# Amplifier_Mixer.net
KiCad netlist of a schematic drawn in EAGLE
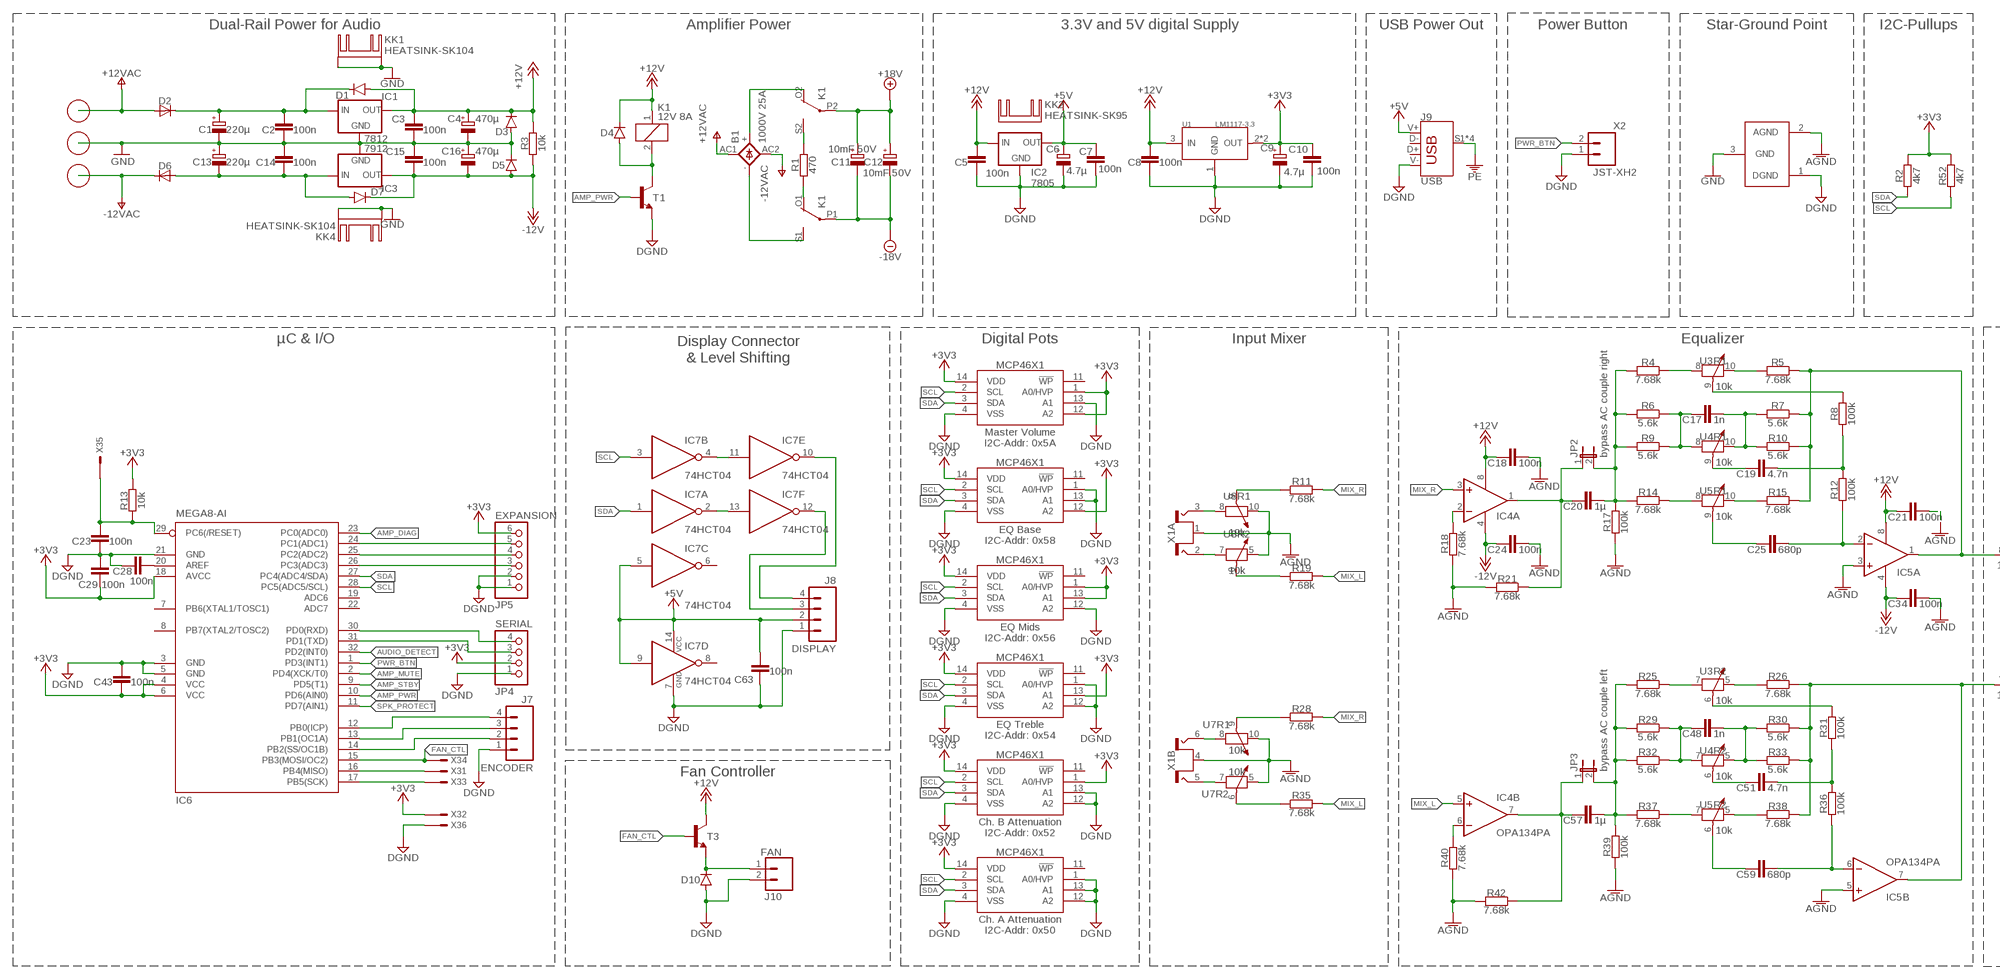
[diagram p0: schematic, sheet 1, part 1 of 2]
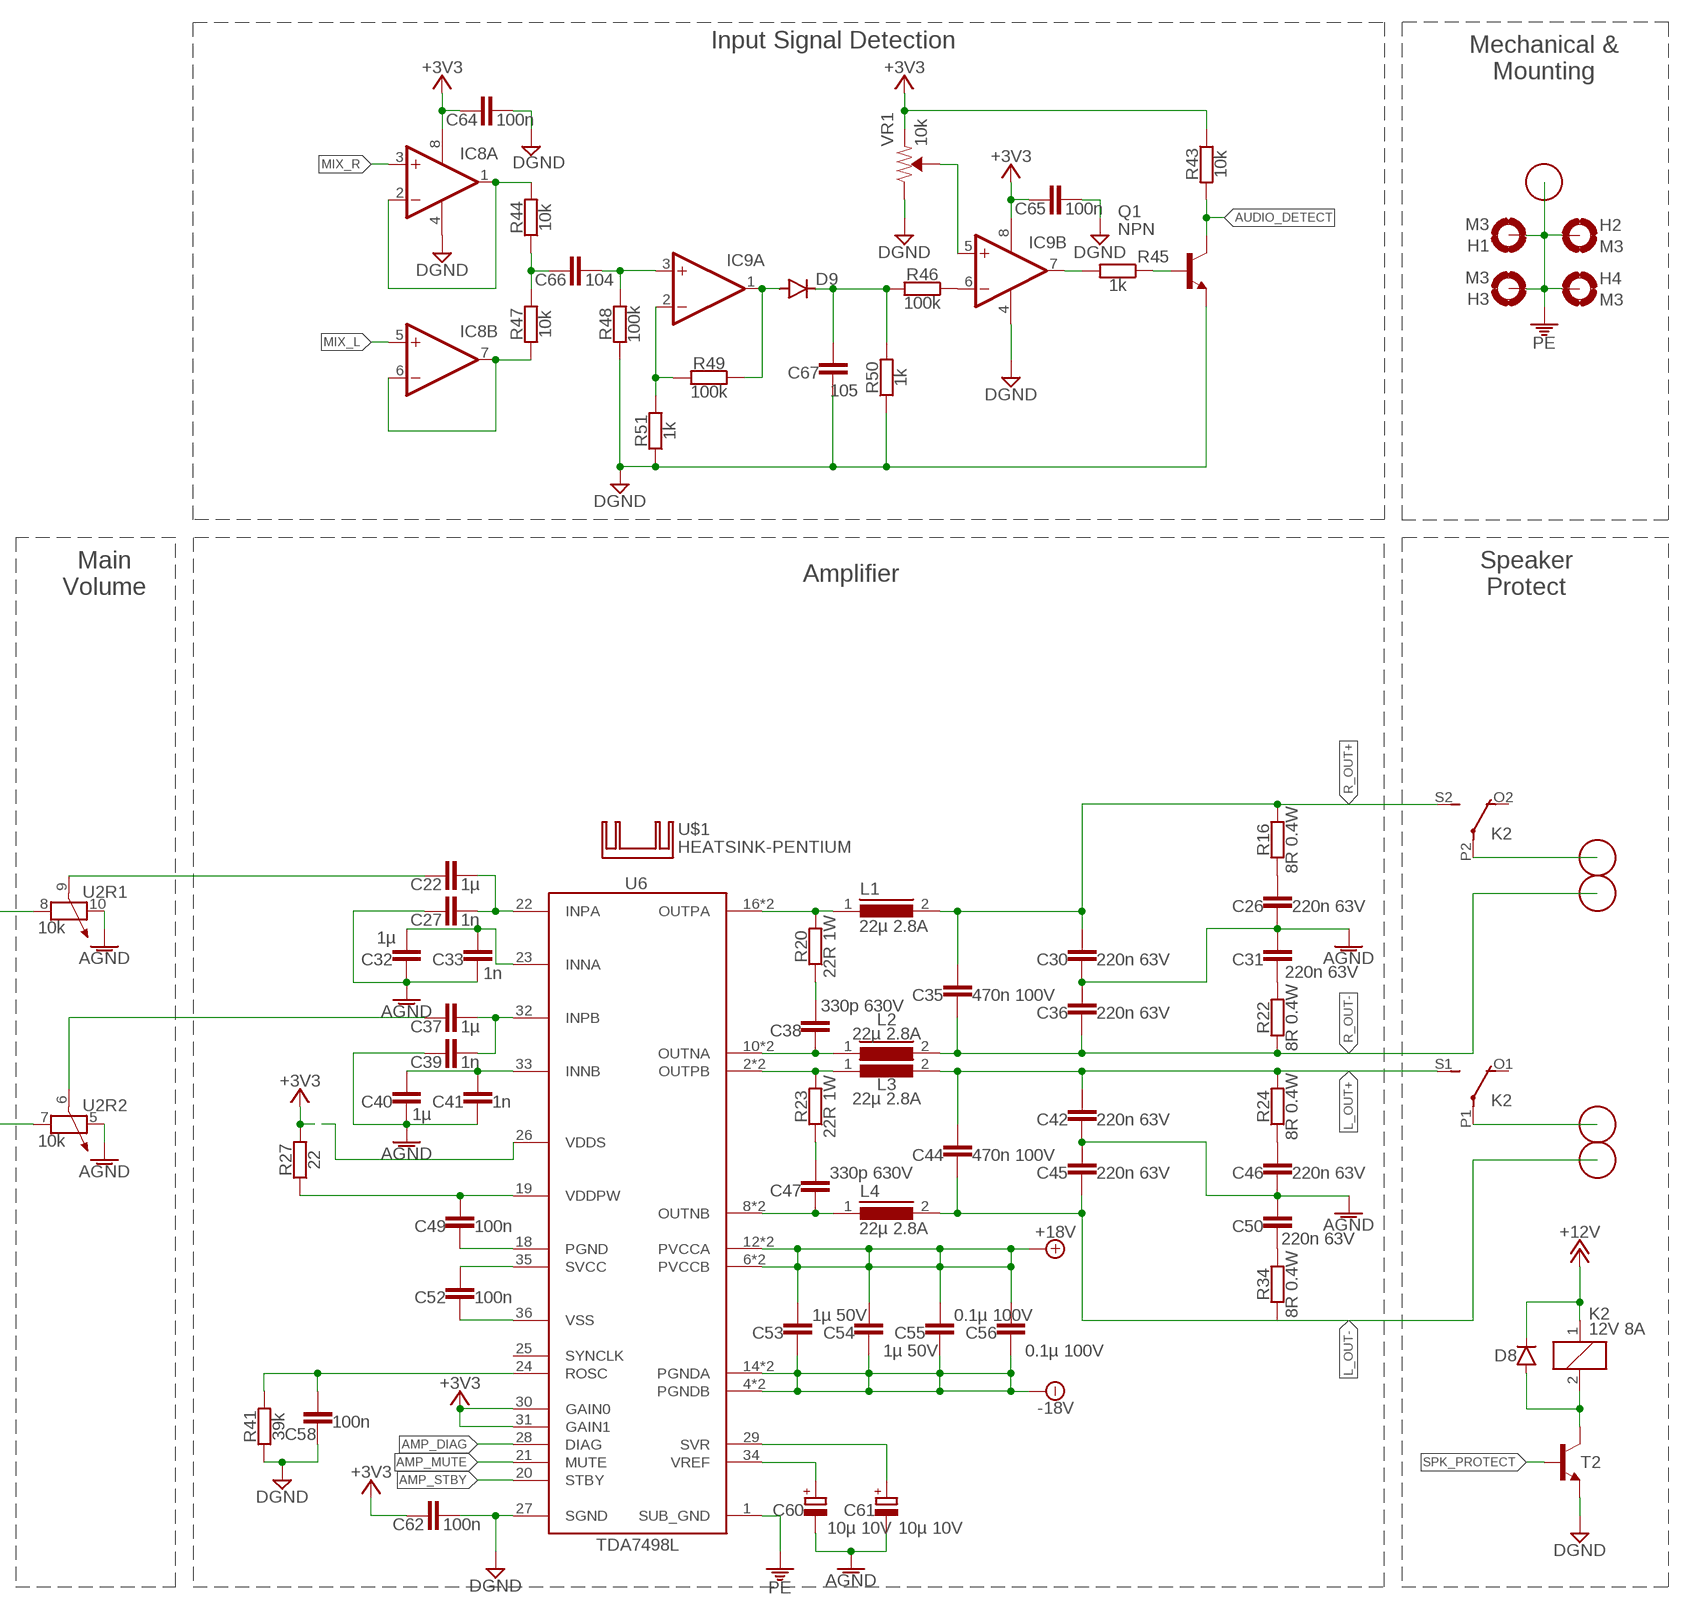
[diagram p1: schematic, sheet 1, part 2 of 2]

(export (version "E")
  (design (tool "Eeschema 10.0.6"))
  (components
    (comp (ref "B1")
      (value "1000V 25A")
      (footprint "eagle-import:FB100")
      (libsource (lib "eagle-import") (part "RECTIFIER-FB100"))
    )
    (comp (ref "C1")
      (value "220µ")
      (footprint "eagle-import:175TMP-0810")
      (libsource (lib "eagle-import") (part "CPOL-EU175TMP-0810"))
    )
    (comp (ref "C2")
      (value "100n")
      (footprint "eagle-import:C0603")
      (libsource (lib "eagle-import") (part "C-EUC0603"))
    )
    (comp (ref "C3")
      (value "100n")
      (footprint "eagle-import:C0603")
      (libsource (lib "eagle-import") (part "C-EUC0603"))
    )
    (comp (ref "C4")
      (value "470µ")
      (footprint "eagle-import:175TMP-0810")
      (libsource (lib "eagle-import") (part "CPOL-EU175TMP-0810"))
    )
    (comp (ref "C5")
      (value "100n")
      (footprint "eagle-import:C0603")
      (libsource (lib "eagle-import") (part "C-EUC0603"))
    )
    (comp (ref "C6")
      (value "4.7µ")
      (footprint "eagle-import:153CLV-0505")
      (libsource (lib "eagle-import") (part "CPOL-EU153CLV-0505"))
    )
    (comp (ref "C7")
      (value "100n")
      (footprint "eagle-import:C0603")
      (libsource (lib "eagle-import") (part "C-EUC0603"))
    )
    (comp (ref "C8")
      (value "100n")
      (footprint "eagle-import:C0603")
      (libsource (lib "eagle-import") (part "C-EUC0603"))
    )
    (comp (ref "C9")
      (value "4.7µ")
      (footprint "eagle-import:153CLV-0505")
      (libsource (lib "eagle-import") (part "CPOL-EU153CLV-0505"))
    )
    (comp (ref "C10")
      (value "100n")
      (footprint "eagle-import:C0603")
      (libsource (lib "eagle-import") (part "C-EUC0603"))
    )
    (comp (ref "C11")
      (value "10mF 50V")
      (footprint "eagle-import:EB35D")
      (libsource (lib "eagle-import") (part "TEAPO-SLG109M050S1A5T"))
    )
    (comp (ref "C12")
      (value "10mF 50V")
      (footprint "eagle-import:EB35D")
      (libsource (lib "eagle-import") (part "TEAPO-SLG109M050S1A5T"))
    )
    (comp (ref "C13")
      (value "220µ")
      (footprint "eagle-import:175TMP-0810")
      (libsource (lib "eagle-import") (part "CPOL-EU175TMP-0810"))
    )
    (comp (ref "C14")
      (value "100n")
      (footprint "eagle-import:C0603")
      (libsource (lib "eagle-import") (part "C-EUC0603"))
    )
    (comp (ref "C15")
      (value "100n")
      (footprint "eagle-import:C0603")
      (libsource (lib "eagle-import") (part "C-EUC0603"))
    )
    (comp (ref "C16")
      (value "470µ")
      (footprint "eagle-import:175TMP-0810")
      (libsource (lib "eagle-import") (part "CPOL-EU175TMP-0810"))
    )
    (comp (ref "C17")
      (value "1n")
      (footprint "eagle-import:C050-025X075")
      (libsource (lib "eagle-import") (part "C-EU050-025X075"))
    )
    (comp (ref "C18")
      (value "100n")
      (footprint "eagle-import:C0603")
      (libsource (lib "eagle-import") (part "C-EUC0603"))
    )
    (comp (ref "C19")
      (value "4.7n")
      (footprint "eagle-import:C075-032X103")
      (libsource (lib "eagle-import") (part "C-EU075-032X103"))
    )
    (comp (ref "C20")
      (value "1µ")
      (footprint "eagle-import:C050-050X075")
      (libsource (lib "eagle-import") (part "C-EU050-050X075"))
    )
    (comp (ref "C21")
      (value "100n")
      (footprint "eagle-import:C0603")
      (libsource (lib "eagle-import") (part "C-EUC0603"))
    )
    (comp (ref "C22")
      (value "1µ")
      (footprint "eagle-import:C050-050X075")
      (libsource (lib "eagle-import") (part "C-EU050-050X075"))
    )
    (comp (ref "C23")
      (value "100n")
      (footprint "eagle-import:C0603")
      (libsource (lib "eagle-import") (part "C-EUC0603"))
    )
    (comp (ref "C24")
      (value "100n")
      (footprint "eagle-import:C0603")
      (libsource (lib "eagle-import") (part "C-EUC0603"))
    )
    (comp (ref "C25")
      (value "680p")
      (footprint "eagle-import:C050-045X075")
      (libsource (lib "eagle-import") (part "C-EU050-045X075"))
    )
    (comp (ref "C26")
      (value "220n 63V")
      (footprint "eagle-import:C050-025X075")
      (libsource (lib "eagle-import") (part "C-EU050-025X075"))
    )
    (comp (ref "C27")
      (value "1n")
      (footprint "eagle-import:C050-025X075")
      (libsource (lib "eagle-import") (part "C-EU050-025X075"))
    )
    (comp (ref "C28")
      (value "100n")
      (footprint "eagle-import:C0603")
      (libsource (lib "eagle-import") (part "C-EUC0603"))
    )
    (comp (ref "C29")
      (value "100n")
      (footprint "eagle-import:C0603")
      (libsource (lib "eagle-import") (part "C-EUC0603"))
    )
    (comp (ref "C30")
      (value "220n 63V")
      (footprint "eagle-import:C050-025X075")
      (libsource (lib "eagle-import") (part "C-EU050-025X075"))
    )
    (comp (ref "C31")
      (value "220n 63V")
      (footprint "eagle-import:C050-025X075")
      (libsource (lib "eagle-import") (part "C-EU050-025X075"))
    )
    (comp (ref "C32")
      (value "1µ")
      (footprint "eagle-import:C050-050X075")
      (libsource (lib "eagle-import") (part "C-EU050-050X075"))
    )
    (comp (ref "C33")
      (value "1n")
      (footprint "eagle-import:C050-025X075")
      (libsource (lib "eagle-import") (part "C-EU050-025X075"))
    )
    (comp (ref "C34")
      (value "100n")
      (footprint "eagle-import:C0603")
      (libsource (lib "eagle-import") (part "C-EUC0603"))
    )
    (comp (ref "C35")
      (value "470n 100V")
      (footprint "eagle-import:C050-045X075")
      (libsource (lib "eagle-import") (part "C-EU050-045X075"))
    )
    (comp (ref "C36")
      (value "220n 63V")
      (footprint "eagle-import:C050-025X075")
      (libsource (lib "eagle-import") (part "C-EU050-025X075"))
    )
    (comp (ref "C37")
      (value "1µ")
      (footprint "eagle-import:C050-050X075")
      (libsource (lib "eagle-import") (part "C-EU050-050X075"))
    )
    (comp (ref "C38")
      (value "330p 630V")
      (footprint "eagle-import:C050-045X075")
      (libsource (lib "eagle-import") (part "C-EU050-045X075"))
    )
    (comp (ref "C39")
      (value "1n")
      (footprint "eagle-import:C050-025X075")
      (libsource (lib "eagle-import") (part "C-EU050-025X075"))
    )
    (comp (ref "C40")
      (value "1µ")
      (footprint "eagle-import:C050-050X075")
      (libsource (lib "eagle-import") (part "C-EU050-050X075"))
    )
    (comp (ref "C41")
      (value "1n")
      (footprint "eagle-import:C050-025X075")
      (libsource (lib "eagle-import") (part "C-EU050-025X075"))
    )
    (comp (ref "C42")
      (value "220n 63V")
      (footprint "eagle-import:C050-025X075")
      (libsource (lib "eagle-import") (part "C-EU050-025X075"))
    )
    (comp (ref "C43")
      (value "100n")
      (footprint "eagle-import:C0603")
      (libsource (lib "eagle-import") (part "C-EUC0603"))
    )
    (comp (ref "C44")
      (value "470n 100V")
      (footprint "eagle-import:C050-045X075")
      (libsource (lib "eagle-import") (part "C-EU050-045X075"))
    )
    (comp (ref "C45")
      (value "220n 63V")
      (footprint "eagle-import:C050-025X075")
      (libsource (lib "eagle-import") (part "C-EU050-025X075"))
    )
    (comp (ref "C46")
      (value "220n 63V")
      (footprint "eagle-import:C050-025X075")
      (libsource (lib "eagle-import") (part "C-EU050-025X075"))
    )
    (comp (ref "C47")
      (value "330p 630V")
      (footprint "eagle-import:C050-045X075")
      (libsource (lib "eagle-import") (part "C-EU050-045X075"))
    )
    (comp (ref "C48")
      (value "1n")
      (footprint "eagle-import:C050-025X075")
      (libsource (lib "eagle-import") (part "C-EU050-025X075"))
    )
    (comp (ref "C49")
      (value "100n")
      (footprint "eagle-import:C0603")
      (libsource (lib "eagle-import") (part "C-EUC0603"))
    )
    (comp (ref "C50")
      (value "220n 63V")
      (footprint "eagle-import:C050-025X075")
      (libsource (lib "eagle-import") (part "C-EU050-025X075"))
    )
    (comp (ref "C51")
      (value "4.7n")
      (footprint "eagle-import:C075-032X103")
      (libsource (lib "eagle-import") (part "C-EU075-032X103"))
    )
    (comp (ref "C52")
      (value "100n")
      (footprint "eagle-import:C0603")
      (libsource (lib "eagle-import") (part "C-EUC0603"))
    )
    (comp (ref "C53")
      (value "1µ 50V")
      (footprint "eagle-import:C1206K")
      (fields (field (name "SPICEPREFIX") "Kemet C1206C105K5RAC7800+"))
      (libsource (lib "eagle-import") (part "C-EUC1206K"))
    )
    (comp (ref "C54")
      (value "1µ 50V")
      (footprint "eagle-import:C1206K")
      (fields (field (name "SPICEPREFIX") "Kemet C1206C105K5RAC7800+"))
      (libsource (lib "eagle-import") (part "C-EUC1206K"))
    )
    (comp (ref "C55")
      (value "0.1µ 100V")
      (footprint "eagle-import:C1206K")
      (fields (field (name "SPICEPREFIX") "Kemet C1206C104K1RAC7800+"))
      (libsource (lib "eagle-import") (part "C-EUC1206K"))
    )
    (comp (ref "C56")
      (value "0.1µ 100V")
      (footprint "eagle-import:C1206K")
      (fields (field (name "SPICEPREFIX") "Kemet C1206C104K1RAC7800+"))
      (libsource (lib "eagle-import") (part "C-EUC1206K"))
    )
    (comp (ref "C57")
      (value "1µ")
      (footprint "eagle-import:C050-050X075")
      (libsource (lib "eagle-import") (part "C-EU050-050X075"))
    )
    (comp (ref "C58")
      (value "100n")
      (footprint "eagle-import:C0603")
      (libsource (lib "eagle-import") (part "C-EUC0603"))
    )
    (comp (ref "C59")
      (value "680p")
      (footprint "eagle-import:C050-045X075")
      (libsource (lib "eagle-import") (part "C-EU050-045X075"))
    )
    (comp (ref "C60")
      (value "10µ 10V")
      (footprint "eagle-import:153CLV-0505")
      (libsource (lib "eagle-import") (part "CPOL-EU153CLV-0505"))
    )
    (comp (ref "C61")
      (value "10µ 10V")
      (footprint "eagle-import:153CLV-0505")
      (libsource (lib "eagle-import") (part "CPOL-EU153CLV-0505"))
    )
    (comp (ref "C62")
      (value "100n")
      (footprint "eagle-import:C0603")
      (libsource (lib "eagle-import") (part "C-EUC0603"))
    )
    (comp (ref "C63")
      (value "100n")
      (footprint "eagle-import:C0603")
      (libsource (lib "eagle-import") (part "C-EUC0603"))
    )
    (comp (ref "C64")
      (value "100n")
      (footprint "eagle-import:C0603")
      (libsource (lib "eagle-import") (part "C-EUC0603"))
    )
    (comp (ref "C65")
      (value "100n")
      (footprint "eagle-import:C0603")
      (libsource (lib "eagle-import") (part "C-EUC0603"))
    )
    (comp (ref "C66")
      (value "104")
      (footprint "eagle-import:C0603")
      (libsource (lib "eagle-import") (part "C-EUC0603"))
    )
    (comp (ref "C67")
      (value "105")
      (footprint "eagle-import:C0603")
      (libsource (lib "eagle-import") (part "C-EUC0603"))
    )
    (comp (ref "D1")
      (value "DIODEBAS16")
      (footprint "eagle-import:SOD-323")
      (libsource (lib "eagle-import") (part "DIODEBAS16"))
    )
    (comp (ref "D2")
      (value "DIODE")
      (footprint "eagle-import:SODFL5024X231")
      (libsource (lib "eagle-import") (part "DIODE"))
    )
    (comp (ref "D3")
      (value "DIODEBAS16")
      (footprint "eagle-import:SOD-323")
      (libsource (lib "eagle-import") (part "DIODEBAS16"))
    )
    (comp (ref "D4")
      (value "DIODEBAS16")
      (footprint "eagle-import:SOD-323")
      (libsource (lib "eagle-import") (part "DIODEBAS16"))
    )
    (comp (ref "D5")
      (value "DIODEBAS16")
      (footprint "eagle-import:SOD-323")
      (libsource (lib "eagle-import") (part "DIODEBAS16"))
    )
    (comp (ref "D6")
      (value "DIODE")
      (footprint "eagle-import:SODFL5024X231")
      (libsource (lib "eagle-import") (part "DIODE"))
    )
    (comp (ref "D7")
      (value "DIODEBAS16")
      (footprint "eagle-import:SOD-323")
      (libsource (lib "eagle-import") (part "DIODEBAS16"))
    )
    (comp (ref "D8")
      (value "DIODEBAS16")
      (footprint "eagle-import:SOD-323")
      (libsource (lib "eagle-import") (part "DIODEBAS16"))
    )
    (comp (ref "D9")
      (value "DIODE-SOD123")
      (footprint "eagle-import:SOD123")
      (libsource (lib "eagle-import") (part "DIODE-SOD123"))
    )
    (comp (ref "D10")
      (value "DIODEBAS16")
      (footprint "eagle-import:SOD-323")
      (libsource (lib "eagle-import") (part "DIODEBAS16"))
    )
    (comp (ref "H1")
      (value "M3")
      (footprint "eagle-import:3,0-PAD")
      (libsource (lib "eagle-import") (part "HOLE-3MM-PAD"))
    )
    (comp (ref "H2")
      (value "M3")
      (footprint "eagle-import:3,0-PAD")
      (libsource (lib "eagle-import") (part "HOLE-3MM-PAD"))
    )
    (comp (ref "H3")
      (value "M3")
      (footprint "eagle-import:3,0-PAD")
      (libsource (lib "eagle-import") (part "HOLE-3MM-PAD"))
    )
    (comp (ref "H4")
      (value "M3")
      (footprint "eagle-import:3,0-PAD")
      (libsource (lib "eagle-import") (part "HOLE-3MM-PAD"))
    )
    (comp (ref "IC1")
      (value "7812")
      (footprint "eagle-import:78XXS")
      (libsource (lib "eagle-import") (part "78XXS"))
    )
    (comp (ref "IC2")
      (value "7805")
      (footprint "eagle-import:78XXS")
      (libsource (lib "eagle-import") (part "78XXS"))
    )
    (comp (ref "IC3")
      (value "7912")
      (footprint "eagle-import:79XXS")
      (libsource (lib "eagle-import") (part "79XXS"))
    )
    (comp (ref "IC4")
      (value "OPA134PA")
      (footprint "eagle-import:DIL08")
      (fields (field (name "CONRAD") "1011117 - 62"))
      (libsource (lib "eagle-import") (part "LM358N"))
    )
    (comp (ref "IC5")
      (value "OPA134PA")
      (footprint "eagle-import:DIL08")
      (fields (field (name "CONRAD") "1011117 - 62"))
      (libsource (lib "eagle-import") (part "LM358N"))
    )
    (comp (ref "IC6")
      (value "MEGA8-AI")
      (footprint "eagle-import:TQFP32-08")
      (fields (field (name "MPN") "ATMEGA8-16AU"))
      (libsource (lib "eagle-import") (part "MEGA8-AI"))
    )
    (comp (ref "IC7")
      (value "74HCT04")
      (footprint "eagle-import:SO14")
      (libsource (lib "eagle-import") (part "7404D"))
    )
    (comp (ref "IC8")
      (value "2AMP_P8+4D")
      (footprint "eagle-import:SO08")
      (libsource (lib "eagle-import") (part "2AMP_P8+4D"))
    )
    (comp (ref "IC9")
      (value "2AMP_P8+4D")
      (footprint "eagle-import:SO08")
      (libsource (lib "eagle-import") (part "2AMP_P8+4D"))
    )
    (comp (ref "J1")
      (value "+12AC")
      (footprint "eagle-import:TE-726386")
      (libsource (lib "eagle-import") (part "TERMINAL-1"))
    )
    (comp (ref "J2")
      (value "0V")
      (footprint "eagle-import:TE-726386")
      (libsource (lib "eagle-import") (part "TERMINAL-1"))
    )
    (comp (ref "J3")
      (value "-12AC")
      (footprint "eagle-import:TE-726386")
      (libsource (lib "eagle-import") (part "TERMINAL-1"))
    )
    (comp (ref "J4")
      (value "PE")
      (footprint "eagle-import:TE-726386")
      (libsource (lib "eagle-import") (part "TERMINAL-1"))
    )
    (comp (ref "J5")
      (value "TERMINAL-BLOCK-2PLUG-IN")
      (footprint "eagle-import:MSTBV2")
      (libsource (lib "eagle-import") (part "TERMINAL-BLOCK-2PLUG-IN"))
    )
    (comp (ref "J6")
      (value "TERMINAL-BLOCK-2PLUG-IN")
      (footprint "eagle-import:MSTBV2")
      (libsource (lib "eagle-import") (part "TERMINAL-BLOCK-2PLUG-IN"))
    )
    (comp (ref "J7")
      (value "ENCODER")
      (footprint "eagle-import:JST-4-PTH-VERT")
      (libsource (lib "eagle-import") (part "JST-XH4"))
    )
    (comp (ref "J8")
      (value "DISPLAY")
      (footprint "eagle-import:JST-4-PTH-VERT")
      (libsource (lib "eagle-import") (part "JST-XH4"))
    )
    (comp (ref "J9")
      (value "USB")
      (footprint "eagle-import:ECON-USBBUVA")
      (libsource (lib "eagle-import") (part "USB"))
    )
    (comp (ref "J10")
      (value "FAN")
      (footprint "eagle-import:JST-2-PTH-VERT")
      (libsource (lib "eagle-import") (part "JST-XH2"))
    )
    (comp (ref "JP1")
      (value "GND_CONNECT")
      (footprint "eagle-import:GND_CONNECT")
      (libsource (lib "eagle-import") (part "GND_CONNECT"))
    )
    (comp (ref "JP2")
      (value "bypass AC couple right")
      (footprint "eagle-import:JP1")
      (libsource (lib "eagle-import") (part "JP1E"))
    )
    (comp (ref "JP3")
      (value "bypass AC couple left")
      (footprint "eagle-import:JP1")
      (libsource (lib "eagle-import") (part "JP1E"))
    )
    (comp (ref "JP4")
      (value "SERIAL")
      (footprint "eagle-import:1X04")
      (libsource (lib "eagle-import") (part "PINHD-1X4"))
    )
    (comp (ref "JP5")
      (value "EXPANSION")
      (footprint "eagle-import:1X06")
      (libsource (lib "eagle-import") (part "PINHD-1X6"))
    )
    (comp (ref "K1")
      (value "12V 8A")
      (footprint "eagle-import:F4052")
      (fields (field (name "CONRAD") "629528 - 62") (field (name "SPEC") "Hongfa HF115F/012-2ZS4A"))
      (libsource (lib "eagle-import") (part "RELAY-F40.52"))
    )
    (comp (ref "K2")
      (value "12V 8A")
      (footprint "eagle-import:F4052")
      (fields (field (name "CONRAD") "629528 - 62") (field (name "SPEC") "Hongfa HF115F/012-2ZS4A"))
      (libsource (lib "eagle-import") (part "RELAY-F40.52"))
    )
    (comp (ref "KK1")
      (value "HEATSINK-SK104")
      (footprint "eagle-import:SK104-PAD")
      (libsource (lib "eagle-import") (part "HEATSINK-SK104"))
    )
    (comp (ref "KK2")
      (value "HEATSINK-SK95")
      (footprint "eagle-import:SK95-2M3")
      (libsource (lib "eagle-import") (part "HEATSINK-SK95"))
    )
    (comp (ref "KK4")
      (value "HEATSINK-SK104")
      (footprint "eagle-import:SK104-PAD")
      (libsource (lib "eagle-import") (part "HEATSINK-SK104"))
    )
    (comp (ref "L1")
      (value "22µ 2.8A")
      (footprint "eagle-import:INDUCTOR-12MM")
      (libsource (lib "eagle-import") (part "INDUCTOR12MM-SMD"))
    )
    (comp (ref "L2")
      (value "22µ 2.8A")
      (footprint "eagle-import:INDUCTOR-12MM")
      (libsource (lib "eagle-import") (part "INDUCTOR12MM-SMD"))
    )
    (comp (ref "L3")
      (value "22µ 2.8A")
      (footprint "eagle-import:INDUCTOR-12MM")
      (libsource (lib "eagle-import") (part "INDUCTOR12MM-SMD"))
    )
    (comp (ref "L4")
      (value "22µ 2.8A")
      (footprint "eagle-import:INDUCTOR-12MM")
      (libsource (lib "eagle-import") (part "INDUCTOR12MM-SMD"))
    )
    (comp (ref "Q1")
      (value "NPN")
      (footprint "eagle-import:SOT23-BEC")
      (libsource (lib "eagle-import") (part "BC817SMD-16LT1"))
    )
    (comp (ref "R1")
      (value "470")
      (footprint "eagle-import:0617_22")
      (libsource (lib "eagle-import") (part "RESISTOR-0617-22"))
    )
    (comp (ref "R2")
      (value "4k7")
      (footprint "eagle-import:R0603")
      (libsource (lib "eagle-import") (part "R-EU_R0603"))
    )
    (comp (ref "R3")
      (value "10k")
      (footprint "eagle-import:R1206")
      (libsource (lib "eagle-import") (part "R-EU_R1206"))
    )
    (comp (ref "R4")
      (value "7.68k")
      (footprint "eagle-import:MINI_MELF-0207W")
      (libsource (lib "eagle-import") (part "R-EU_MELF0207W"))
    )
    (comp (ref "R5")
      (value "7.68k")
      (footprint "eagle-import:MINI_MELF-0207W")
      (libsource (lib "eagle-import") (part "R-EU_MELF0207W"))
    )
    (comp (ref "R6")
      (value "5.6k")
      (footprint "eagle-import:MINI_MELF-0207W")
      (libsource (lib "eagle-import") (part "R-EU_MELF0207W"))
    )
    (comp (ref "R7")
      (value "5.6k")
      (footprint "eagle-import:MINI_MELF-0207W")
      (libsource (lib "eagle-import") (part "R-EU_MELF0207W"))
    )
    (comp (ref "R8")
      (value "100k")
      (footprint "eagle-import:MINI_MELF-0204W")
      (libsource (lib "eagle-import") (part "R-EU_MELF0204W"))
    )
    (comp (ref "R9")
      (value "5.6k")
      (footprint "eagle-import:MINI_MELF-0207W")
      (libsource (lib "eagle-import") (part "R-EU_MELF0207W"))
    )
    (comp (ref "R10")
      (value "5.6k")
      (footprint "eagle-import:MINI_MELF-0207W")
      (libsource (lib "eagle-import") (part "R-EU_MELF0207W"))
    )
    (comp (ref "R11")
      (value "7.68k")
      (footprint "eagle-import:MINI_MELF-0207W")
      (libsource (lib "eagle-import") (part "R-EU_MELF0207W"))
    )
    (comp (ref "R12")
      (value "100k")
      (footprint "eagle-import:MINI_MELF-0204W")
      (libsource (lib "eagle-import") (part "R-EU_MELF0204W"))
    )
    (comp (ref "R13")
      (value "10k")
      (footprint "eagle-import:R0603")
      (libsource (lib "eagle-import") (part "R-EU_R0603"))
    )
    (comp (ref "R14")
      (value "7.68k")
      (footprint "eagle-import:MINI_MELF-0207W")
      (libsource (lib "eagle-import") (part "R-EU_MELF0207W"))
    )
    (comp (ref "R15")
      (value "7.68k")
      (footprint "eagle-import:MINI_MELF-0207W")
      (libsource (lib "eagle-import") (part "R-EU_MELF0207W"))
    )
    (comp (ref "R16")
      (value "8R 0.4W")
      (footprint "eagle-import:MINI_MELF-0204W")
      (libsource (lib "eagle-import") (part "R-EU_MELF0204W"))
    )
    (comp (ref "R17")
      (value "100k")
      (footprint "eagle-import:MINI_MELF-0204W")
      (libsource (lib "eagle-import") (part "R-EU_MELF0204W"))
    )
    (comp (ref "R18")
      (value "7.68k")
      (footprint "eagle-import:MINI_MELF-0207W")
      (libsource (lib "eagle-import") (part "R-EU_MELF0207W"))
    )
    (comp (ref "R19")
      (value "7.68k")
      (footprint "eagle-import:MINI_MELF-0207W")
      (libsource (lib "eagle-import") (part "R-EU_MELF0207W"))
    )
    (comp (ref "R20")
      (value "22R 1W")
      (footprint "eagle-import:MINI_MELF-0207W")
      (libsource (lib "eagle-import") (part "R-EU_MELF0207W"))
    )
    (comp (ref "R21")
      (value "7.68k")
      (footprint "eagle-import:MINI_MELF-0207W")
      (libsource (lib "eagle-import") (part "R-EU_MELF0207W"))
    )
    (comp (ref "R22")
      (value "8R 0.4W")
      (footprint "eagle-import:MINI_MELF-0204W")
      (libsource (lib "eagle-import") (part "R-EU_MELF0204W"))
    )
    (comp (ref "R23")
      (value "22R 1W")
      (footprint "eagle-import:MINI_MELF-0207W")
      (libsource (lib "eagle-import") (part "R-EU_MELF0207W"))
    )
    (comp (ref "R24")
      (value "8R 0.4W")
      (footprint "eagle-import:MINI_MELF-0204W")
      (libsource (lib "eagle-import") (part "R-EU_MELF0204W"))
    )
    (comp (ref "R25")
      (value "7.68k")
      (footprint "eagle-import:MINI_MELF-0207W")
      (libsource (lib "eagle-import") (part "R-EU_MELF0207W"))
    )
    (comp (ref "R26")
      (value "7.68k")
      (footprint "eagle-import:MINI_MELF-0207W")
      (libsource (lib "eagle-import") (part "R-EU_MELF0207W"))
    )
    (comp (ref "R27")
      (value "22")
      (footprint "eagle-import:R0603")
      (libsource (lib "eagle-import") (part "R-EU_R0603"))
    )
    (comp (ref "R28")
      (value "7.68k")
      (footprint "eagle-import:MINI_MELF-0207W")
      (libsource (lib "eagle-import") (part "R-EU_MELF0207W"))
    )
    (comp (ref "R29")
      (value "5.6k")
      (footprint "eagle-import:MINI_MELF-0207W")
      (libsource (lib "eagle-import") (part "R-EU_MELF0207W"))
    )
    (comp (ref "R30")
      (value "5.6k")
      (footprint "eagle-import:MINI_MELF-0207W")
      (libsource (lib "eagle-import") (part "R-EU_MELF0207W"))
    )
    (comp (ref "R31")
      (value "100k")
      (footprint "eagle-import:MINI_MELF-0204W")
      (libsource (lib "eagle-import") (part "R-EU_MELF0204W"))
    )
    (comp (ref "R32")
      (value "5.6k")
      (footprint "eagle-import:MINI_MELF-0207W")
      (libsource (lib "eagle-import") (part "R-EU_MELF0207W"))
    )
    (comp (ref "R33")
      (value "5.6k")
      (footprint "eagle-import:MINI_MELF-0207W")
      (libsource (lib "eagle-import") (part "R-EU_MELF0207W"))
    )
    (comp (ref "R34")
      (value "8R 0.4W")
      (footprint "eagle-import:MINI_MELF-0204W")
      (libsource (lib "eagle-import") (part "R-EU_MELF0204W"))
    )
    (comp (ref "R35")
      (value "7.68k")
      (footprint "eagle-import:MINI_MELF-0207W")
      (libsource (lib "eagle-import") (part "R-EU_MELF0207W"))
    )
    (comp (ref "R36")
      (value "100k")
      (footprint "eagle-import:MINI_MELF-0204W")
      (libsource (lib "eagle-import") (part "R-EU_MELF0204W"))
    )
    (comp (ref "R37")
      (value "7.68k")
      (footprint "eagle-import:MINI_MELF-0207W")
      (libsource (lib "eagle-import") (part "R-EU_MELF0207W"))
    )
    (comp (ref "R38")
      (value "7.68k")
      (footprint "eagle-import:MINI_MELF-0207W")
      (libsource (lib "eagle-import") (part "R-EU_MELF0207W"))
    )
    (comp (ref "R39")
      (value "100k")
      (footprint "eagle-import:MINI_MELF-0204W")
      (libsource (lib "eagle-import") (part "R-EU_MELF0204W"))
    )
    (comp (ref "R40")
      (value "7.68k")
      (footprint "eagle-import:MINI_MELF-0207W")
      (libsource (lib "eagle-import") (part "R-EU_MELF0207W"))
    )
    (comp (ref "R41")
      (value "39k")
      (footprint "eagle-import:R0603")
      (libsource (lib "eagle-import") (part "R-EU_R0603"))
    )
    (comp (ref "R42")
      (value "7.68k")
      (footprint "eagle-import:MINI_MELF-0207W")
      (libsource (lib "eagle-import") (part "R-EU_MELF0207W"))
    )
    (comp (ref "R43")
      (value "10k")
      (footprint "eagle-import:R0603")
      (libsource (lib "eagle-import") (part "R-EU_R0603"))
    )
    (comp (ref "R44")
      (value "10k")
      (footprint "eagle-import:R0603")
      (libsource (lib "eagle-import") (part "R-EU_R0603"))
    )
    (comp (ref "R45")
      (value "1k")
      (footprint "eagle-import:R0603")
      (libsource (lib "eagle-import") (part "R-EU_R0603"))
    )
    (comp (ref "R46")
      (value "100k")
      (footprint "eagle-import:R0603")
      (libsource (lib "eagle-import") (part "R-EU_R0603"))
    )
    (comp (ref "R47")
      (value "10k")
      (footprint "eagle-import:R0603")
      (libsource (lib "eagle-import") (part "R-EU_R0603"))
    )
    (comp (ref "R48")
      (value "100k")
      (footprint "eagle-import:R0603")
      (libsource (lib "eagle-import") (part "R-EU_R0603"))
    )
    (comp (ref "R49")
      (value "100k")
      (footprint "eagle-import:R0603")
      (libsource (lib "eagle-import") (part "R-EU_R0603"))
    )
    (comp (ref "R50")
      (value "1k")
      (footprint "eagle-import:R0603")
      (libsource (lib "eagle-import") (part "R-EU_R0603"))
    )
    (comp (ref "R51")
      (value "1k")
      (footprint "eagle-import:R0603")
      (libsource (lib "eagle-import") (part "R-EU_R0603"))
    )
    (comp (ref "R52")
      (value "4k7")
      (footprint "eagle-import:R0603")
      (libsource (lib "eagle-import") (part "R-EU_R0603"))
    )
    (comp (ref "T1")
      (value "BC817-16-NPN-SOT23-BEC")
      (footprint "eagle-import:SOT23-BEC")
      (libsource (lib "eagle-import") (part "-NPN-SOT23-BECBC817-16"))
    )
    (comp (ref "T2")
      (value "BC817-16-NPN-SOT23-BEC")
      (footprint "eagle-import:SOT23-BEC")
      (libsource (lib "eagle-import") (part "-NPN-SOT23-BECBC817-16"))
    )
    (comp (ref "T3")
      (value "BC817-16-NPN-SOT23-BEC")
      (footprint "eagle-import:SOT23-BEC")
      (libsource (lib "eagle-import") (part "-NPN-SOT23-BECBC817-16"))
    )
    (comp (ref "U$1")
      (value "HEATSINK-PENTIUM")
      (footprint "eagle-import:HEATSINK-PENTIUM")
      (libsource (lib "eagle-import") (part "HEATSINK-PENTIUM"))
    )
    (comp (ref "U1")
      (value "LM1117-3.3")
      (footprint "eagle-import:SOT-223")
      (fields (field (name "MPN") "CJT1117-3.3"))
      (libsource (lib "eagle-import") (part "PMIC-CJT1117-3.3(SOT223)"))
    )
    (comp (ref "U2")
      (value "10k")
      (footprint "eagle-import:SOP65P640X120-14")
      (libsource (lib "eagle-import") (part "MCP46X1"))
    )
    (comp (ref "U3")
      (value "10k")
      (footprint "eagle-import:SOP65P640X120-14")
      (libsource (lib "eagle-import") (part "MCP46X1"))
    )
    (comp (ref "U4")
      (value "10k")
      (footprint "eagle-import:SOP65P640X120-14")
      (libsource (lib "eagle-import") (part "MCP46X1"))
    )
    (comp (ref "U5")
      (value "10k")
      (footprint "eagle-import:SOP65P640X120-14")
      (libsource (lib "eagle-import") (part "MCP46X1"))
    )
    (comp (ref "U6")
      (value "TDA7498L")
      (footprint "eagle-import:SOP50P1010X245-36")
      (libsource (lib "eagle-import") (part "TDA7498L"))
    )
    (comp (ref "U7")
      (value "10k")
      (footprint "eagle-import:SOP65P640X120-14")
      (libsource (lib "eagle-import") (part "MCP46X1"))
    )
    (comp (ref "U8")
      (value "10k")
      (footprint "eagle-import:SOP65P640X120-14")
      (libsource (lib "eagle-import") (part "MCP46X1"))
    )
    (comp (ref "VR1")
      (value "10k")
      (footprint "eagle-import:TRIMPOT-SMD-TC33X")
      (libsource (lib "eagle-import") (part "TRIMPOT-SMD-3MM-OPEN-1/10W-25%"))
    )
    (comp (ref "X1")
      (value "RCA-4-CHANNEL")
      (footprint "eagle-import:BKL-072385")
      (libsource (lib "eagle-import") (part "RCA-4-CHANNEL"))
    )
    (comp (ref "X2")
      (value "JST-XH2")
      (footprint "eagle-import:JST-2-PTH-VERT")
      (libsource (lib "eagle-import") (part "JST-XH2"))
    )
    (comp (ref "X3")
      (value "ICSP")
      (footprint "eagle-import:057-006-1")
      (libsource (lib "eagle-import") (part "CONN-IDC-6"))
    )
  )
  (nets
    (net (code "1") (name "+3V3") (class "Default")
      (node (ref "C10") (pin "1") (pinfunction "1_1") (pintype "passive"))
      (node (ref "C29") (pin "1") (pinfunction "1_1") (pintype "passive"))
      (node (ref "C43") (pin "1") (pinfunction "1_1") (pintype "passive"))
      (node (ref "C62") (pin "2") (pinfunction "2_2") (pintype "passive"))
      (node (ref "C64") (pin "1") (pinfunction "1_1") (pintype "passive"))
      (node (ref "C65") (pin "1") (pinfunction "1_1") (pintype "passive"))
      (node (ref "C9") (pin "+") (pinfunction "+_+") (pintype "passive"))
      (node (ref "IC6") (pin "18") (pinfunction "AVCC_18") (pintype "power_in"))
      (node (ref "IC6") (pin "4") (pinfunction "VCC_4") (pintype "power_in"))
      (node (ref "IC6") (pin "6") (pinfunction "VCC_6") (pintype "power_in"))
      (node (ref "IC8") (pin "8") (pinfunction "V+_8") (pintype "power_in"))
      (node (ref "IC9") (pin "8") (pinfunction "V+_8") (pintype "power_in"))
      (node (ref "JP4") (pin "2") (pinfunction "2_2") (pintype "passive"))
      (node (ref "JP5") (pin "6") (pinfunction "6_6") (pintype "passive"))
      (node (ref "R13") (pin "2") (pinfunction "2_2") (pintype "passive"))
      (node (ref "R2") (pin "2") (pinfunction "2_2") (pintype "passive"))
      (node (ref "R27") (pin "2") (pinfunction "2_2") (pintype "passive"))
      (node (ref "R43") (pin "1") (pinfunction "1_1") (pintype "passive"))
      (node (ref "R52") (pin "2") (pinfunction "2_2") (pintype "passive"))
      (node (ref "U1") (pin "2") (pinfunction "OUT_2") (pintype "bidirectional"))
      (node (ref "U1") (pin "TER") (pinfunction "OUT_TER") (pintype "bidirectional"))
      (node (ref "U2") (pin "1") (pinfunction "A0/HVP_1") (pintype "bidirectional"))
      (node (ref "U2") (pin "12") (pinfunction "A2_12") (pintype "bidirectional"))
      (node (ref "U2") (pin "14") (pinfunction "VDD_14") (pintype "bidirectional"))
      (node (ref "U3") (pin "12") (pinfunction "A2_12") (pintype "bidirectional"))
      (node (ref "U3") (pin "14") (pinfunction "VDD_14") (pintype "bidirectional"))
      (node (ref "U4") (pin "1") (pinfunction "A0/HVP_1") (pintype "bidirectional"))
      (node (ref "U4") (pin "13") (pinfunction "A1_13") (pintype "bidirectional"))
      (node (ref "U4") (pin "14") (pinfunction "VDD_14") (pintype "bidirectional"))
      (node (ref "U5") (pin "13") (pinfunction "A1_13") (pintype "bidirectional"))
      (node (ref "U5") (pin "14") (pinfunction "VDD_14") (pintype "bidirectional"))
      (node (ref "U6") (pin "26") (pinfunction "VDDS_26") (pintype "bidirectional"))
      (node (ref "U6") (pin "30") (pinfunction "GAIN0_30") (pintype "bidirectional"))
      (node (ref "U6") (pin "31") (pinfunction "GAIN1_31") (pintype "bidirectional"))
      (node (ref "U7") (pin "1") (pinfunction "A0/HVP_1") (pintype "bidirectional"))
      (node (ref "U7") (pin "14") (pinfunction "VDD_14") (pintype "bidirectional"))
      (node (ref "U8") (pin "14") (pinfunction "VDD_14") (pintype "bidirectional"))
      (node (ref "VR1") (pin "3") (pinfunction "CCW_3") (pintype "passive"))
      (node (ref "X3") (pin "2") (pinfunction "S_2") (pintype "passive"))
    )
    (net (code "2") (name "+5V") (class "Default")
      (node (ref "C6") (pin "+") (pinfunction "+_+") (pintype "passive"))
      (node (ref "C63") (pin "2") (pinfunction "2_2") (pintype "passive"))
      (node (ref "C7") (pin "1") (pinfunction "1_1") (pintype "passive"))
      (node (ref "IC2") (pin "OUT") (pinfunction "OUT_OUT") (pintype "passive"))
      (node (ref "IC7") (pin "14") (pinfunction "VCC_14") (pintype "power_in"))
      (node (ref "IC7") (pin "5") (pinfunction "I_5") (pintype "input"))
      (node (ref "IC7") (pin "9") (pinfunction "I_9") (pintype "input"))
      (node (ref "J8") (pin "2") (pinfunction "2_2") (pintype "passive"))
      (node (ref "J9") (pin "V+") (pinfunction "VBUS_V+") (pintype "power_in"))
    )
    (net (code "3") (name "+12V") (class "Default")
      (node (ref "C18") (pin "1") (pinfunction "1_1") (pintype "passive"))
      (node (ref "C21") (pin "1") (pinfunction "1_1") (pintype "passive"))
      (node (ref "C3") (pin "1") (pinfunction "1_1") (pintype "passive"))
      (node (ref "C4") (pin "+") (pinfunction "+_+") (pintype "passive"))
      (node (ref "C5") (pin "1") (pinfunction "1_1") (pintype "passive"))
      (node (ref "C8") (pin "1") (pinfunction "1_1") (pintype "passive"))
      (node (ref "D1") (pin "A") (pinfunction "A_A") (pintype "passive"))
      (node (ref "D3") (pin "C") (pinfunction "C_C") (pintype "passive"))
      (node (ref "D4") (pin "C") (pinfunction "C_C") (pintype "passive"))
      (node (ref "D8") (pin "C") (pinfunction "C_C") (pintype "passive"))
      (node (ref "IC1") (pin "OUT") (pinfunction "OUT_OUT") (pintype "passive"))
      (node (ref "IC2") (pin "IN") (pinfunction "IN_IN") (pintype "input"))
      (node (ref "IC4") (pin "8") (pinfunction "V+_8") (pintype "power_in"))
      (node (ref "IC5") (pin "8") (pinfunction "V+_8") (pintype "power_in"))
      (node (ref "K1") (pin "1") (pinfunction "1_1") (pintype "passive"))
      (node (ref "K2") (pin "1") (pinfunction "1_1") (pintype "passive"))
      (node (ref "R3") (pin "1") (pinfunction "1_1") (pintype "passive"))
      (node (ref "T3") (pin "C") (pinfunction "C_C") (pintype "passive"))
      (node (ref "U1") (pin "3") (pinfunction "IN_3") (pintype "bidirectional"))
    )
    (net (code "4") (name "+12VAC") (class "Default")
      (node (ref "B1") (pin "AC1") (pinfunction "AC1_AC1") (pintype "passive"))
      (node (ref "D2") (pin "A") (pinfunction "A_A") (pintype "passive"))
      (node (ref "J1") (pin "P$1") (pinfunction "P$1_P$1") (pintype "bidirectional"))
      (node (ref "J1") (pin "P$2") (pinfunction "P$1_P$2") (pintype "bidirectional"))
    )
    (net (code "5") (name "+18V") (class "Default")
      (node (ref "C11") (pin "+") (pinfunction "+_+") (pintype "passive"))
      (node (ref "C12") (pin "+") (pinfunction "+_+") (pintype "passive"))
      (node (ref "C53") (pin "1") (pinfunction "1_1") (pintype "passive"))
      (node (ref "C54") (pin "1") (pinfunction "1_1") (pintype "passive"))
      (node (ref "C55") (pin "1") (pinfunction "1_1") (pintype "passive"))
      (node (ref "C56") (pin "1") (pinfunction "1_1") (pintype "passive"))
      (node (ref "K1") (pin "P2") (pinfunction "P_P2") (pintype "passive"))
      (node (ref "U6") (pin "12") (pinfunction "PVCCA_12") (pintype "bidirectional"))
      (node (ref "U6") (pin "13") (pinfunction "PVCCA_13") (pintype "bidirectional"))
      (node (ref "U6") (pin "6") (pinfunction "PVCCB_6") (pintype "bidirectional"))
      (node (ref "U6") (pin "7") (pinfunction "PVCCB_7") (pintype "bidirectional"))
    )
    (net (code "6") (name "-12V") (class "Default")
      (node (ref "C15") (pin "2") (pinfunction "2_2") (pintype "passive"))
      (node (ref "C16") (pin "-") (pinfunction "-_-") (pintype "passive"))
      (node (ref "C24") (pin "1") (pinfunction "1_1") (pintype "passive"))
      (node (ref "C34") (pin "1") (pinfunction "1_1") (pintype "passive"))
      (node (ref "D5") (pin "A") (pinfunction "A_A") (pintype "passive"))
      (node (ref "D7") (pin "C") (pinfunction "C_C") (pintype "passive"))
      (node (ref "IC3") (pin "OUT") (pinfunction "OUT_OUT") (pintype "passive"))
      (node (ref "IC4") (pin "4") (pinfunction "V-_4") (pintype "power_in"))
      (node (ref "IC5") (pin "4") (pinfunction "V-_4") (pintype "power_in"))
      (node (ref "R3") (pin "2") (pinfunction "2_2") (pintype "passive"))
    )
    (net (code "7") (name "-12VAC") (class "Default")
      (node (ref "B1") (pin "AC2") (pinfunction "AC2_AC2") (pintype "passive"))
      (node (ref "D6") (pin "C") (pinfunction "C_C") (pintype "passive"))
      (node (ref "J3") (pin "P$1") (pinfunction "P$1_P$1") (pintype "bidirectional"))
      (node (ref "J3") (pin "P$2") (pinfunction "P$1_P$2") (pintype "bidirectional"))
    )
    (net (code "8") (name "-18V") (class "Default")
      (node (ref "C11") (pin "-") (pinfunction "-_-") (pintype "passive"))
      (node (ref "C12") (pin "-") (pinfunction "-_-") (pintype "passive"))
      (node (ref "C53") (pin "2") (pinfunction "2_2") (pintype "passive"))
      (node (ref "C54") (pin "2") (pinfunction "2_2") (pintype "passive"))
      (node (ref "C55") (pin "2") (pinfunction "2_2") (pintype "passive"))
      (node (ref "C56") (pin "2") (pinfunction "2_2") (pintype "passive"))
      (node (ref "K1") (pin "P1") (pinfunction "P_P1") (pintype "passive"))
      (node (ref "U6") (pin "14") (pinfunction "PGNDA_14") (pintype "bidirectional"))
      (node (ref "U6") (pin "15") (pinfunction "PGNDA_15") (pintype "bidirectional"))
      (node (ref "U6") (pin "4") (pinfunction "PGNDB_4") (pintype "bidirectional"))
      (node (ref "U6") (pin "5") (pinfunction "PGNDB_5") (pintype "bidirectional"))
    )
    (net (code "9") (name "AGND") (class "Default")
      (node (ref "C18") (pin "2") (pinfunction "2_2") (pintype "passive"))
      (node (ref "C21") (pin "2") (pinfunction "2_2") (pintype "passive"))
      (node (ref "C24") (pin "2") (pinfunction "2_2") (pintype "passive"))
      (node (ref "C26") (pin "2") (pinfunction "2_2") (pintype "passive"))
      (node (ref "C27") (pin "1") (pinfunction "1_1") (pintype "passive"))
      (node (ref "C30") (pin "2") (pinfunction "2_2") (pintype "passive"))
      (node (ref "C31") (pin "1") (pinfunction "1_1") (pintype "passive"))
      (node (ref "C32") (pin "1") (pinfunction "1_1") (pintype "passive"))
      (node (ref "C33") (pin "1") (pinfunction "1_1") (pintype "passive"))
      (node (ref "C34") (pin "2") (pinfunction "2_2") (pintype "passive"))
      (node (ref "C36") (pin "1") (pinfunction "1_1") (pintype "passive"))
      (node (ref "C39") (pin "1") (pinfunction "1_1") (pintype "passive"))
      (node (ref "C40") (pin "1") (pinfunction "1_1") (pintype "passive"))
      (node (ref "C41") (pin "1") (pinfunction "1_1") (pintype "passive"))
      (node (ref "C42") (pin "2") (pinfunction "2_2") (pintype "passive"))
      (node (ref "C45") (pin "1") (pinfunction "1_1") (pintype "passive"))
      (node (ref "C46") (pin "2") (pinfunction "2_2") (pintype "passive"))
      (node (ref "C50") (pin "1") (pinfunction "1_1") (pintype "passive"))
      (node (ref "C60") (pin "-") (pinfunction "-_-") (pintype "passive"))
      (node (ref "C61") (pin "-") (pinfunction "-_-") (pintype "passive"))
      (node (ref "IC5") (pin "3") (pinfunction "+IN_3") (pintype "input"))
      (node (ref "IC5") (pin "5") (pinfunction "+IN_5") (pintype "input"))
      (node (ref "JP1") (pin "2") (pinfunction "AGND_2") (pintype "bidirectional"))
      (node (ref "R17") (pin "1") (pinfunction "1_1") (pintype "passive"))
      (node (ref "R18") (pin "2") (pinfunction "2_2") (pintype "passive"))
      (node (ref "R21") (pin "2") (pinfunction "2_2") (pintype "passive"))
      (node (ref "R39") (pin "1") (pinfunction "1_1") (pintype "passive"))
      (node (ref "R40") (pin "2") (pinfunction "2_2") (pintype "passive"))
      (node (ref "R42") (pin "2") (pinfunction "2_2") (pintype "passive"))
      (node (ref "U2") (pin "10") (pinfunction "B_10") (pintype "passive"))
      (node (ref "U2") (pin "5") (pinfunction "B_5") (pintype "passive"))
      (node (ref "U7") (pin "10") (pinfunction "B_10") (pintype "passive"))
      (node (ref "U7") (pin "5") (pinfunction "B_5") (pintype "passive"))
      (node (ref "U8") (pin "10") (pinfunction "B_10") (pintype "passive"))
      (node (ref "U8") (pin "5") (pinfunction "B_5") (pintype "passive"))
      (node (ref "X1") (pin "1") (pinfunction "S_1") (pintype "passive"))
      (node (ref "X1") (pin "4") (pinfunction "S_4") (pintype "passive"))
    )
    (net (code "10") (name "AMP_DIAG") (class "Default")
      (node (ref "IC6") (pin "23") (pinfunction "PC0(ADC0)_23") (pintype "bidirectional"))
      (node (ref "U6") (pin "28") (pinfunction "DIAG_28") (pintype "bidirectional"))
    )
    (net (code "11") (name "AMP_MUTE") (class "Default")
      (node (ref "IC6") (pin "2") (pinfunction "PD4(XCK/T0)_2") (pintype "bidirectional"))
      (node (ref "U6") (pin "21") (pinfunction "MUTE_21") (pintype "bidirectional"))
    )
    (net (code "12") (name "AMP_PWR") (class "Default")
      (node (ref "IC6") (pin "10") (pinfunction "PD6(AIN0)_10") (pintype "bidirectional"))
      (node (ref "T1") (pin "B") (pinfunction "B_B") (pintype "passive"))
    )
    (net (code "13") (name "AMP_STBY") (class "Default")
      (node (ref "IC6") (pin "9") (pinfunction "PD5(T1)_9") (pintype "bidirectional"))
      (node (ref "U6") (pin "20") (pinfunction "STBY_20") (pintype "bidirectional"))
    )
    (net (code "14") (name "AUDIO_DETECT") (class "Default")
      (node (ref "IC6") (pin "32") (pinfunction "PD2(INT0)_32") (pintype "bidirectional"))
      (node (ref "Q1") (pin "C") (pinfunction "C_C") (pintype "passive"))
      (node (ref "R43") (pin "2") (pinfunction "2_2") (pintype "passive"))
    )
    (net (code "15") (name "DGND") (class "Default")
      (node (ref "C10") (pin "2") (pinfunction "2_2") (pintype "passive"))
      (node (ref "C23") (pin "1") (pinfunction "1_1") (pintype "passive"))
      (node (ref "C28") (pin "2") (pinfunction "2_2") (pintype "passive"))
      (node (ref "C29") (pin "2") (pinfunction "2_2") (pintype "passive"))
      (node (ref "C43") (pin "2") (pinfunction "2_2") (pintype "passive"))
      (node (ref "C5") (pin "2") (pinfunction "2_2") (pintype "passive"))
      (node (ref "C58") (pin "2") (pinfunction "2_2") (pintype "passive"))
      (node (ref "C6") (pin "-") (pinfunction "-_-") (pintype "passive"))
      (node (ref "C62") (pin "1") (pinfunction "1_1") (pintype "passive"))
      (node (ref "C63") (pin "1") (pinfunction "1_1") (pintype "passive"))
      (node (ref "C64") (pin "2") (pinfunction "2_2") (pintype "passive"))
      (node (ref "C65") (pin "2") (pinfunction "2_2") (pintype "passive"))
      (node (ref "C67") (pin "1") (pinfunction "1_1") (pintype "passive"))
      (node (ref "C7") (pin "2") (pinfunction "2_2") (pintype "passive"))
      (node (ref "C8") (pin "2") (pinfunction "2_2") (pintype "passive"))
      (node (ref "C9") (pin "-") (pinfunction "-_-") (pintype "passive"))
      (node (ref "D10") (pin "A") (pinfunction "A_A") (pintype "passive"))
      (node (ref "IC2") (pin "GND") (pinfunction "GND_GND") (pintype "input"))
      (node (ref "IC6") (pin "21") (pinfunction "GND_21") (pintype "power_in"))
      (node (ref "IC6") (pin "3") (pinfunction "GND_3") (pintype "power_in"))
      (node (ref "IC6") (pin "5") (pinfunction "GND_5") (pintype "power_in"))
      (node (ref "IC7") (pin "7") (pinfunction "GND_7") (pintype "power_in"))
      (node (ref "IC8") (pin "4") (pinfunction "V-_4") (pintype "power_in"))
      (node (ref "IC9") (pin "4") (pinfunction "V-_4") (pintype "power_in"))
      (node (ref "J10") (pin "2") (pinfunction "2_2") (pintype "passive"))
      (node (ref "J7") (pin "1") (pinfunction "1_1") (pintype "passive"))
      (node (ref "J8") (pin "1") (pinfunction "1_1") (pintype "passive"))
      (node (ref "J9") (pin "V-") (pinfunction "GND_V-") (pintype "power_in"))
      (node (ref "JP1") (pin "1") (pinfunction "DGND_1") (pintype "bidirectional"))
      (node (ref "JP4") (pin "1") (pinfunction "1_1") (pintype "passive"))
      (node (ref "JP5") (pin "1") (pinfunction "1_1") (pintype "passive"))
      (node (ref "JP5") (pin "2") (pinfunction "2_2") (pintype "passive"))
      (node (ref "Q1") (pin "E") (pinfunction "E_E") (pintype "passive"))
      (node (ref "R41") (pin "1") (pinfunction "1_1") (pintype "passive"))
      (node (ref "R48") (pin "1") (pinfunction "1_1") (pintype "passive"))
      (node (ref "R50") (pin "1") (pinfunction "1_1") (pintype "passive"))
      (node (ref "R51") (pin "1") (pinfunction "1_1") (pintype "passive"))
      (node (ref "T1") (pin "E") (pinfunction "E_E") (pintype "passive"))
      (node (ref "T2") (pin "E") (pinfunction "E_E") (pintype "passive"))
      (node (ref "U1") (pin "1") (pinfunction "GND_1") (pintype "bidirectional"))
      (node (ref "U2") (pin "13") (pinfunction "A1_13") (pintype "bidirectional"))
      (node (ref "U2") (pin "4") (pinfunction "VSS_4") (pintype "bidirectional"))
      (node (ref "U3") (pin "1") (pinfunction "A0/HVP_1") (pintype "bidirectional"))
      (node (ref "U3") (pin "13") (pinfunction "A1_13") (pintype "bidirectional"))
      (node (ref "U3") (pin "4") (pinfunction "VSS_4") (pintype "bidirectional"))
      (node (ref "U4") (pin "12") (pinfunction "A2_12") (pintype "bidirectional"))
      (node (ref "U4") (pin "4") (pinfunction "VSS_4") (pintype "bidirectional"))
      (node (ref "U5") (pin "1") (pinfunction "A0/HVP_1") (pintype "bidirectional"))
      (node (ref "U5") (pin "12") (pinfunction "A2_12") (pintype "bidirectional"))
      (node (ref "U5") (pin "4") (pinfunction "VSS_4") (pintype "bidirectional"))
      (node (ref "U6") (pin "27") (pinfunction "SGND_27") (pintype "bidirectional"))
      (node (ref "U7") (pin "12") (pinfunction "A2_12") (pintype "bidirectional"))
      (node (ref "U7") (pin "13") (pinfunction "A1_13") (pintype "bidirectional"))
      (node (ref "U7") (pin "4") (pinfunction "VSS_4") (pintype "bidirectional"))
      (node (ref "U8") (pin "1") (pinfunction "A0/HVP_1") (pintype "bidirectional"))
      (node (ref "U8") (pin "12") (pinfunction "A2_12") (pintype "bidirectional"))
      (node (ref "U8") (pin "13") (pinfunction "A1_13") (pintype "bidirectional"))
      (node (ref "U8") (pin "4") (pinfunction "VSS_4") (pintype "bidirectional"))
      (node (ref "VR1") (pin "1") (pinfunction "CW_1") (pintype "passive"))
      (node (ref "X2") (pin "1") (pinfunction "1_1") (pintype "passive"))
      (node (ref "X3") (pin "6") (pinfunction "S_6") (pintype "passive"))
    )
    (net (code "16") (name "FAN_CTL") (class "Default")
      (node (ref "IC6") (pin "15") (pinfunction "PB3(MOSI/OC2)_15") (pintype "bidirectional"))
      (node (ref "T3") (pin "B") (pinfunction "B_B") (pintype "passive"))
      (node (ref "X3") (pin "4") (pinfunction "S_4") (pintype "passive"))
    )
    (net (code "17") (name "GND") (class "Default")
      (node (ref "C1") (pin "-") (pinfunction "-_-") (pintype "passive"))
      (node (ref "C13") (pin "+") (pinfunction "+_+") (pintype "passive"))
      (node (ref "C14") (pin "1") (pinfunction "1_1") (pintype "passive"))
      (node (ref "C15") (pin "1") (pinfunction "1_1") (pintype "passive"))
      (node (ref "C16") (pin "+") (pinfunction "+_+") (pintype "passive"))
      (node (ref "C2") (pin "2") (pinfunction "2_2") (pintype "passive"))
      (node (ref "C3") (pin "2") (pinfunction "2_2") (pintype "passive"))
      (node (ref "C4") (pin "-") (pinfunction "-_-") (pintype "passive"))
      (node (ref "D3") (pin "A") (pinfunction "A_A") (pintype "passive"))
      (node (ref "D5") (pin "C") (pinfunction "C_C") (pintype "passive"))
      (node (ref "IC1") (pin "GND") (pinfunction "GND_GND") (pintype "input"))
      (node (ref "IC3") (pin "GND") (pinfunction "GND_GND") (pintype "input"))
      (node (ref "J2") (pin "P$1") (pinfunction "P$1_P$1") (pintype "bidirectional"))
      (node (ref "J2") (pin "P$2") (pinfunction "P$1_P$2") (pintype "bidirectional"))
      (node (ref "JP1") (pin "3") (pinfunction "GND_3") (pintype "bidirectional"))
      (node (ref "KK1") (pin "K1") (pinfunction "K_K1") (pintype "passive"))
      (node (ref "KK1") (pin "K2") (pinfunction "K_K2") (pintype "passive"))
      (node (ref "KK4") (pin "K1") (pinfunction "K_K1") (pintype "passive"))
      (node (ref "KK4") (pin "K2") (pinfunction "K_K2") (pintype "passive"))
    )
    (net (code "18") (name "L_OUT+") (class "Default")
      (node (ref "C42") (pin "1") (pinfunction "1_1") (pintype "passive"))
      (node (ref "C44") (pin "1") (pinfunction "1_1") (pintype "passive"))
      (node (ref "K2") (pin "S1") (pinfunction "S_S1") (pintype "passive"))
      (node (ref "L3") (pin "2") (pinfunction "2_2") (pintype "passive"))
      (node (ref "R24") (pin "2") (pinfunction "2_2") (pintype "passive"))
    )
    (net (code "19") (name "L_OUT-") (class "Default")
      (node (ref "C44") (pin "2") (pinfunction "2_2") (pintype "passive"))
      (node (ref "C45") (pin "2") (pinfunction "2_2") (pintype "passive"))
      (node (ref "J6") (pin "2") (pinfunction "P$1_2") (pintype "bidirectional"))
      (node (ref "L4") (pin "2") (pinfunction "2_2") (pintype "passive"))
      (node (ref "R34") (pin "1") (pinfunction "1_1") (pintype "passive"))
    )
    (net (code "20") (name "MIX_L") (class "Default")
      (node (ref "IC4") (pin "5") (pinfunction "+IN_5") (pintype "input"))
      (node (ref "IC8") (pin "5") (pinfunction "+IN_5") (pintype "input"))
      (node (ref "R19") (pin "2") (pinfunction "2_2") (pintype "passive"))
      (node (ref "R35") (pin "2") (pinfunction "2_2") (pintype "passive"))
    )
    (net (code "21") (name "MIX_R") (class "Default")
      (node (ref "IC4") (pin "3") (pinfunction "+IN_3") (pintype "input"))
      (node (ref "IC8") (pin "3") (pinfunction "+IN_3") (pintype "input"))
      (node (ref "R11") (pin "2") (pinfunction "2_2") (pintype "passive"))
      (node (ref "R28") (pin "2") (pinfunction "2_2") (pintype "passive"))
    )
    (net (code "22") (name "Net-(C1-Pad+)") (class "Default")
      (node (ref "C1") (pin "+") (pinfunction "+_+") (pintype "passive"))
      (node (ref "C2") (pin "1") (pinfunction "1_1") (pintype "passive"))
      (node (ref "D1") (pin "C") (pinfunction "C_C") (pintype "passive"))
      (node (ref "D2") (pin "C") (pinfunction "C_C") (pintype "passive"))
      (node (ref "IC1") (pin "IN") (pinfunction "IN_IN") (pintype "input"))
    )
    (net (code "23") (name "Net-(C13-Pad-)") (class "Default")
      (node (ref "C13") (pin "-") (pinfunction "-_-") (pintype "passive"))
      (node (ref "C14") (pin "2") (pinfunction "2_2") (pintype "passive"))
      (node (ref "D6") (pin "A") (pinfunction "A_A") (pintype "passive"))
      (node (ref "D7") (pin "A") (pinfunction "A_A") (pintype "passive"))
      (node (ref "IC3") (pin "IN") (pinfunction "IN_IN") (pintype "input"))
    )
    (net (code "24") (name "Net-(C19-Pad1)") (class "Default")
      (node (ref "C19") (pin "1") (pinfunction "1_1") (pintype "passive"))
      (node (ref "R12") (pin "2") (pinfunction "2_2") (pintype "passive"))
      (node (ref "R8") (pin "1") (pinfunction "1_1") (pintype "passive"))
    )
    (net (code "25") (name "Net-(C20-Pad2)") (class "Default")
      (node (ref "C20") (pin "2") (pinfunction "2_2") (pintype "passive"))
      (node (ref "JP2") (pin "2") (pinfunction "2_2") (pintype "passive"))
      (node (ref "R14") (pin "2") (pinfunction "2_2") (pintype "passive"))
      (node (ref "R17") (pin "2") (pinfunction "2_2") (pintype "passive"))
      (node (ref "R4") (pin "2") (pinfunction "2_2") (pintype "passive"))
      (node (ref "R6") (pin "2") (pinfunction "2_2") (pintype "passive"))
      (node (ref "R9") (pin "2") (pinfunction "2_2") (pintype "passive"))
    )
    (net (code "26") (name "Net-(C26-Pad1)") (class "Default")
      (node (ref "C26") (pin "1") (pinfunction "1_1") (pintype "passive"))
      (node (ref "R16") (pin "1") (pinfunction "1_1") (pintype "passive"))
    )
    (net (code "27") (name "Net-(C31-Pad2)") (class "Default")
      (node (ref "C31") (pin "2") (pinfunction "2_2") (pintype "passive"))
      (node (ref "R22") (pin "2") (pinfunction "2_2") (pintype "passive"))
    )
    (net (code "28") (name "Net-(C38-Pad1)") (class "Default")
      (node (ref "C38") (pin "1") (pinfunction "1_1") (pintype "passive"))
      (node (ref "R20") (pin "1") (pinfunction "1_1") (pintype "passive"))
    )
    (net (code "29") (name "Net-(C38-Pad2)") (class "Default")
      (node (ref "C38") (pin "2") (pinfunction "2_2") (pintype "passive"))
      (node (ref "L2") (pin "1") (pinfunction "1_1") (pintype "passive"))
      (node (ref "U6") (pin "10") (pinfunction "OUTNA_10") (pintype "bidirectional"))
      (node (ref "U6") (pin "11") (pinfunction "OUTNA_11") (pintype "bidirectional"))
    )
    (net (code "30") (name "Net-(C46-Pad1)") (class "Default")
      (node (ref "C46") (pin "1") (pinfunction "1_1") (pintype "passive"))
      (node (ref "R24") (pin "1") (pinfunction "1_1") (pintype "passive"))
    )
    (net (code "31") (name "Net-(C47-Pad1)") (class "Default")
      (node (ref "C47") (pin "1") (pinfunction "1_1") (pintype "passive"))
      (node (ref "R23") (pin "1") (pinfunction "1_1") (pintype "passive"))
    )
    (net (code "32") (name "Net-(C47-Pad2)") (class "Default")
      (node (ref "C47") (pin "2") (pinfunction "2_2") (pintype "passive"))
      (node (ref "L4") (pin "1") (pinfunction "1_1") (pintype "passive"))
      (node (ref "U6") (pin "8") (pinfunction "OUTNB_8") (pintype "bidirectional"))
      (node (ref "U6") (pin "9") (pinfunction "OUTNB_9") (pintype "bidirectional"))
    )
    (net (code "33") (name "Net-(C50-Pad2)") (class "Default")
      (node (ref "C50") (pin "2") (pinfunction "2_2") (pintype "passive"))
      (node (ref "R34") (pin "2") (pinfunction "2_2") (pintype "passive"))
    )
    (net (code "34") (name "Net-(C51-Pad1)") (class "Default")
      (node (ref "C51") (pin "1") (pinfunction "1_1") (pintype "passive"))
      (node (ref "R31") (pin "1") (pinfunction "1_1") (pintype "passive"))
      (node (ref "R36") (pin "2") (pinfunction "2_2") (pintype "passive"))
    )
    (net (code "35") (name "Net-(C57-Pad2)") (class "Default")
      (node (ref "C57") (pin "2") (pinfunction "2_2") (pintype "passive"))
      (node (ref "JP3") (pin "2") (pinfunction "2_2") (pintype "passive"))
      (node (ref "R25") (pin "2") (pinfunction "2_2") (pintype "passive"))
      (node (ref "R29") (pin "2") (pinfunction "2_2") (pintype "passive"))
      (node (ref "R32") (pin "2") (pinfunction "2_2") (pintype "passive"))
      (node (ref "R37") (pin "2") (pinfunction "2_2") (pintype "passive"))
      (node (ref "R39") (pin "2") (pinfunction "2_2") (pintype "passive"))
    )
    (net (code "36") (name "Net-(C66-Pad1)") (class "Default")
      (node (ref "C66") (pin "1") (pinfunction "1_1") (pintype "passive"))
      (node (ref "R44") (pin "1") (pinfunction "1_1") (pintype "passive"))
      (node (ref "R47") (pin "2") (pinfunction "2_2") (pintype "passive"))
    )
    (net (code "37") (name "Net-(C67-Pad2)") (class "Default")
      (node (ref "C67") (pin "2") (pinfunction "2_2") (pintype "passive"))
      (node (ref "D9") (pin "C") (pinfunction "C_C") (pintype "passive"))
      (node (ref "R46") (pin "2") (pinfunction "2_2") (pintype "passive"))
      (node (ref "R50") (pin "2") (pinfunction "2_2") (pintype "passive"))
    )
    (net (code "38") (name "Net-(D4-PadA)") (class "Default")
      (node (ref "D4") (pin "A") (pinfunction "A_A") (pintype "passive"))
      (node (ref "K1") (pin "2") (pinfunction "2_2") (pintype "passive"))
      (node (ref "T1") (pin "C") (pinfunction "C_C") (pintype "passive"))
    )
    (net (code "39") (name "Net-(D8-PadA)") (class "Default")
      (node (ref "D8") (pin "A") (pinfunction "A_A") (pintype "passive"))
      (node (ref "K2") (pin "2") (pinfunction "2_2") (pintype "passive"))
      (node (ref "T2") (pin "C") (pinfunction "C_C") (pintype "passive"))
    )
    (net (code "40") (name "Net-(D10-PadC)") (class "Default")
      (node (ref "D10") (pin "C") (pinfunction "C_C") (pintype "passive"))
      (node (ref "J10") (pin "1") (pinfunction "1_1") (pintype "passive"))
      (node (ref "T3") (pin "E") (pinfunction "E_E") (pintype "passive"))
    )
    (net (code "41") (name "Net-(IC4A--IN)") (class "Default")
      (node (ref "IC4") (pin "2") (pinfunction "-IN_2") (pintype "input"))
      (node (ref "R18") (pin "1") (pinfunction "1_1") (pintype "passive"))
    )
    (net (code "42") (name "Net-(IC4A-OUT)") (class "Default")
      (node (ref "C20") (pin "1") (pinfunction "1_1") (pintype "passive"))
      (node (ref "IC4") (pin "1") (pinfunction "OUT_1") (pintype "output"))
      (node (ref "JP2") (pin "1") (pinfunction "1_1") (pintype "passive"))
      (node (ref "R21") (pin "1") (pinfunction "1_1") (pintype "passive"))
    )
    (net (code "43") (name "Net-(IC4B--IN)") (class "Default")
      (node (ref "IC4") (pin "6") (pinfunction "-IN_6") (pintype "input"))
      (node (ref "R40") (pin "1") (pinfunction "1_1") (pintype "passive"))
    )
    (net (code "44") (name "Net-(IC4B-OUT)") (class "Default")
      (node (ref "C57") (pin "1") (pinfunction "1_1") (pintype "passive"))
      (node (ref "IC4") (pin "7") (pinfunction "OUT_7") (pintype "output"))
      (node (ref "JP3") (pin "1") (pinfunction "1_1") (pintype "passive"))
      (node (ref "R42") (pin "1") (pinfunction "1_1") (pintype "passive"))
    )
    (net (code "45") (name "Net-(IC5A--IN)") (class "Default")
      (node (ref "C25") (pin "1") (pinfunction "1_1") (pintype "passive"))
      (node (ref "IC5") (pin "2") (pinfunction "-IN_2") (pintype "input"))
      (node (ref "R12") (pin "1") (pinfunction "1_1") (pintype "passive"))
    )
    (net (code "46") (name "Net-(IC5A-OUT)") (class "Default")
      (node (ref "IC5") (pin "1") (pinfunction "OUT_1") (pintype "output"))
      (node (ref "R10") (pin "1") (pinfunction "1_1") (pintype "passive"))
      (node (ref "R15") (pin "1") (pinfunction "1_1") (pintype "passive"))
      (node (ref "R5") (pin "1") (pinfunction "1_1") (pintype "passive"))
      (node (ref "R7") (pin "1") (pinfunction "1_1") (pintype "passive"))
      (node (ref "U2") (pin "8") (pinfunction "A_8") (pintype "passive"))
    )
    (net (code "47") (name "Net-(IC5B--IN)") (class "Default")
      (node (ref "C59") (pin "1") (pinfunction "1_1") (pintype "passive"))
      (node (ref "IC5") (pin "6") (pinfunction "-IN_6") (pintype "input"))
      (node (ref "R36") (pin "1") (pinfunction "1_1") (pintype "passive"))
    )
    (net (code "48") (name "Net-(IC5B-OUT)") (class "Default")
      (node (ref "IC5") (pin "7") (pinfunction "OUT_7") (pintype "output"))
      (node (ref "R26") (pin "1") (pinfunction "1_1") (pintype "passive"))
      (node (ref "R30") (pin "1") (pinfunction "1_1") (pintype "passive"))
      (node (ref "R33") (pin "1") (pinfunction "1_1") (pintype "passive"))
      (node (ref "R38") (pin "1") (pinfunction "1_1") (pintype "passive"))
      (node (ref "U2") (pin "7") (pinfunction "A_7") (pintype "passive"))
    )
    (net (code "49") (name "Net-(IC6-AREF)") (class "Default")
      (node (ref "C28") (pin "1") (pinfunction "1_1") (pintype "passive"))
      (node (ref "IC6") (pin "20") (pinfunction "AREF_20") (pintype "passive"))
    )
    (net (code "50") (name "Net-(IC6-PB0(ICP))") (class "Default")
      (node (ref "IC6") (pin "12") (pinfunction "PB0(ICP)_12") (pintype "bidirectional"))
      (node (ref "J7") (pin "4") (pinfunction "4_4") (pintype "passive"))
    )
    (net (code "51") (name "Net-(IC6-PB1(OC1A))") (class "Default")
      (node (ref "IC6") (pin "13") (pinfunction "PB1(OC1A)_13") (pintype "bidirectional"))
      (node (ref "J7") (pin "3") (pinfunction "3_3") (pintype "passive"))
    )
    (net (code "52") (name "Net-(IC6-PB2(SS{slash}OC1B))") (class "Default")
      (node (ref "IC6") (pin "14") (pinfunction "PB2(SS/OC1B)_14") (pintype "bidirectional"))
      (node (ref "J7") (pin "2") (pinfunction "2_2") (pintype "passive"))
    )
    (net (code "53") (name "Net-(IC6-PB4(MISO))") (class "Default")
      (node (ref "IC6") (pin "16") (pinfunction "PB4(MISO)_16") (pintype "bidirectional"))
      (node (ref "X3") (pin "1") (pinfunction "S_1") (pintype "passive"))
    )
    (net (code "54") (name "Net-(IC6-PB5(SCK))") (class "Default")
      (node (ref "IC6") (pin "17") (pinfunction "PB5(SCK)_17") (pintype "bidirectional"))
      (node (ref "X3") (pin "3") (pinfunction "S_3") (pintype "passive"))
    )
    (net (code "55") (name "Net-(IC6-PC1(ADC1))") (class "Default")
      (node (ref "IC6") (pin "24") (pinfunction "PC1(ADC1)_24") (pintype "bidirectional"))
      (node (ref "JP5") (pin "5") (pinfunction "5_5") (pintype "passive"))
    )
    (net (code "56") (name "Net-(IC6-PC2(ADC2))") (class "Default")
      (node (ref "IC6") (pin "25") (pinfunction "PC2(ADC2)_25") (pintype "bidirectional"))
      (node (ref "JP5") (pin "4") (pinfunction "4_4") (pintype "passive"))
    )
    (net (code "57") (name "Net-(IC6-PC3(ADC3))") (class "Default")
      (node (ref "IC6") (pin "26") (pinfunction "PC3(ADC3)_26") (pintype "bidirectional"))
      (node (ref "JP5") (pin "3") (pinfunction "3_3") (pintype "passive"))
    )
    (net (code "58") (name "Net-(IC6-PC6({slash}RESET))") (class "Default")
      (node (ref "C23") (pin "2") (pinfunction "2_2") (pintype "passive"))
      (node (ref "IC6") (pin "29") (pinfunction "PC6(/RESET)_29") (pintype "bidirectional"))
      (node (ref "R13") (pin "1") (pinfunction "1_1") (pintype "passive"))
      (node (ref "X3") (pin "5") (pinfunction "S_5") (pintype "passive"))
    )
    (net (code "59") (name "Net-(IC6-PD0(RXD))") (class "Default")
      (node (ref "IC6") (pin "30") (pinfunction "PD0(RXD)_30") (pintype "bidirectional"))
      (node (ref "JP4") (pin "4") (pinfunction "4_4") (pintype "passive"))
    )
    (net (code "60") (name "Net-(IC6-PD1(TXD))") (class "Default")
      (node (ref "IC6") (pin "31") (pinfunction "PD1(TXD)_31") (pintype "bidirectional"))
      (node (ref "JP4") (pin "3") (pinfunction "3_3") (pintype "passive"))
    )
    (net (code "61") (name "Net-(IC7A-O)") (class "Default")
      (node (ref "IC7") (pin "13") (pinfunction "I_13") (pintype "input"))
      (node (ref "IC7") (pin "2") (pinfunction "O_2") (pintype "output"))
    )
    (net (code "62") (name "Net-(IC7B-O)") (class "Default")
      (node (ref "IC7") (pin "11") (pinfunction "I_11") (pintype "input"))
      (node (ref "IC7") (pin "4") (pinfunction "O_4") (pintype "output"))
    )
    (net (code "63") (name "Net-(IC7E-O)") (class "Default")
      (node (ref "IC7") (pin "10") (pinfunction "O_10") (pintype "output"))
      (node (ref "J8") (pin "4") (pinfunction "4_4") (pintype "passive"))
    )
    (net (code "64") (name "Net-(IC7F-O)") (class "Default")
      (node (ref "IC7") (pin "12") (pinfunction "O_12") (pintype "output"))
      (node (ref "J8") (pin "3") (pinfunction "3_3") (pintype "passive"))
    )
    (net (code "65") (name "Net-(IC8A--IN)") (class "Default")
      (node (ref "IC8") (pin "1") (pinfunction "OUT_1") (pintype "output"))
      (node (ref "IC8") (pin "2") (pinfunction "-IN_2") (pintype "input"))
      (node (ref "R44") (pin "2") (pinfunction "2_2") (pintype "passive"))
    )
    (net (code "66") (name "Net-(IC8B--IN)") (class "Default")
      (node (ref "IC8") (pin "6") (pinfunction "-IN_6") (pintype "input"))
      (node (ref "IC8") (pin "7") (pinfunction "OUT_7") (pintype "output"))
      (node (ref "R47") (pin "1") (pinfunction "1_1") (pintype "passive"))
    )
    (net (code "67") (name "Net-(IC9A-+IN)") (class "Default")
      (node (ref "C66") (pin "2") (pinfunction "2_2") (pintype "passive"))
      (node (ref "IC9") (pin "3") (pinfunction "+IN_3") (pintype "input"))
      (node (ref "R48") (pin "2") (pinfunction "2_2") (pintype "passive"))
    )
    (net (code "68") (name "Net-(IC9A--IN)") (class "Default")
      (node (ref "IC9") (pin "2") (pinfunction "-IN_2") (pintype "input"))
      (node (ref "R49") (pin "2") (pinfunction "2_2") (pintype "passive"))
      (node (ref "R51") (pin "2") (pinfunction "2_2") (pintype "passive"))
    )
    (net (code "69") (name "Net-(IC9A-OUT)") (class "Default")
      (node (ref "D9") (pin "A") (pinfunction "A_A") (pintype "passive"))
      (node (ref "IC9") (pin "1") (pinfunction "OUT_1") (pintype "output"))
      (node (ref "R49") (pin "1") (pinfunction "1_1") (pintype "passive"))
    )
    (net (code "70") (name "Net-(IC9B-+IN)") (class "Default")
      (node (ref "IC9") (pin "5") (pinfunction "+IN_5") (pintype "input"))
      (node (ref "VR1") (pin "2") (pinfunction "WIPER_2") (pintype "passive"))
    )
    (net (code "71") (name "Net-(IC9B--IN)") (class "Default")
      (node (ref "IC9") (pin "6") (pinfunction "-IN_6") (pintype "input"))
      (node (ref "R46") (pin "1") (pinfunction "1_1") (pintype "passive"))
    )
    (net (code "72") (name "Net-(IC9B-OUT)") (class "Default")
      (node (ref "IC9") (pin "7") (pinfunction "OUT_7") (pintype "output"))
      (node (ref "R45") (pin "2") (pinfunction "2_2") (pintype "passive"))
    )
    (net (code "73") (name "Net-(J5A-P$1)") (class "Default")
      (node (ref "J5") (pin "1") (pinfunction "P$1_1") (pintype "bidirectional"))
      (node (ref "K2") (pin "P2") (pinfunction "P_P2") (pintype "passive"))
    )
    (net (code "74") (name "Net-(J6A-P$1)") (class "Default")
      (node (ref "J6") (pin "1") (pinfunction "P$1_1") (pintype "bidirectional"))
      (node (ref "K2") (pin "P1") (pinfunction "P_P1") (pintype "passive"))
    )
    (net (code "75") (name "Net-(K1B-O)") (class "Default")
      (node (ref "K1") (pin "O1") (pinfunction "O_O1") (pintype "passive"))
      (node (ref "R1") (pin "2") (pinfunction "2_2") (pintype "passive"))
    )
    (net (code "76") (name "Net-(K1B-S)") (class "Default")
      (node (ref "B1") (pin "-") (pinfunction "-_-") (pintype "passive"))
      (node (ref "K1") (pin "S1") (pinfunction "S_S1") (pintype "passive"))
    )
    (net (code "77") (name "Net-(K1C-O)") (class "Default")
      (node (ref "B1") (pin "+") (pinfunction "+_+") (pintype "passive"))
      (node (ref "K1") (pin "O2") (pinfunction "O_O2") (pintype "passive"))
    )
    (net (code "78") (name "Net-(K1C-S)") (class "Default")
      (node (ref "K1") (pin "S2") (pinfunction "S_S2") (pintype "passive"))
      (node (ref "R1") (pin "1") (pinfunction "1_1") (pintype "passive"))
    )
    (net (code "79") (name "Net-(L1-Pad1)") (class "Default")
      (node (ref "L1") (pin "1") (pinfunction "1_1") (pintype "passive"))
      (node (ref "R20") (pin "2") (pinfunction "2_2") (pintype "passive"))
      (node (ref "U6") (pin "16") (pinfunction "OUTPA_16") (pintype "bidirectional"))
      (node (ref "U6") (pin "17") (pinfunction "OUTPA_17") (pintype "bidirectional"))
    )
    (net (code "80") (name "Net-(L3-Pad1)") (class "Default")
      (node (ref "L3") (pin "1") (pinfunction "1_1") (pintype "passive"))
      (node (ref "R23") (pin "2") (pinfunction "2_2") (pintype "passive"))
      (node (ref "U6") (pin "2") (pinfunction "OUTPB_2") (pintype "bidirectional"))
      (node (ref "U6") (pin "3") (pinfunction "OUTPB_3") (pintype "bidirectional"))
    )
    (net (code "81") (name "Net-(Q1-PadB)") (class "Default")
      (node (ref "Q1") (pin "B") (pinfunction "B_B") (pintype "passive"))
      (node (ref "R45") (pin "1") (pinfunction "1_1") (pintype "passive"))
    )
    (net (code "82") (name "Net-(U2B-W)") (class "Default")
      (node (ref "C22") (pin "1") (pinfunction "1_1") (pintype "passive"))
      (node (ref "U2") (pin "9") (pinfunction "W_9") (pintype "passive"))
    )
    (net (code "83") (name "Net-(U2C-W)") (class "Default")
      (node (ref "C37") (pin "1") (pinfunction "1_1") (pintype "passive"))
      (node (ref "U2") (pin "6") (pinfunction "W_6") (pintype "passive"))
    )
    (net (code "84") (name "Net-(U3B-A)") (class "Default")
      (node (ref "R4") (pin "1") (pinfunction "1_1") (pintype "passive"))
      (node (ref "U3") (pin "8") (pinfunction "A_8") (pintype "passive"))
    )
    (net (code "85") (name "Net-(U3B-B)") (class "Default")
      (node (ref "R5") (pin "2") (pinfunction "2_2") (pintype "passive"))
      (node (ref "U3") (pin "10") (pinfunction "B_10") (pintype "passive"))
    )
    (net (code "86") (name "Net-(U3B-W)") (class "Default")
      (node (ref "R8") (pin "2") (pinfunction "2_2") (pintype "passive"))
      (node (ref "U3") (pin "9") (pinfunction "W_9") (pintype "passive"))
    )
    (net (code "87") (name "Net-(U3C-A)") (class "Default")
      (node (ref "R25") (pin "1") (pinfunction "1_1") (pintype "passive"))
      (node (ref "U3") (pin "7") (pinfunction "A_7") (pintype "passive"))
    )
    (net (code "88") (name "Net-(U3C-B)") (class "Default")
      (node (ref "R26") (pin "2") (pinfunction "2_2") (pintype "passive"))
      (node (ref "U3") (pin "5") (pinfunction "B_5") (pintype "passive"))
    )
    (net (code "89") (name "Net-(U3C-W)") (class "Default")
      (node (ref "R31") (pin "2") (pinfunction "2_2") (pintype "passive"))
      (node (ref "U3") (pin "6") (pinfunction "W_6") (pintype "passive"))
    )
    (net (code "90") (name "Net-(U4B-A)") (class "Default")
      (node (ref "C17") (pin "1") (pinfunction "1_1") (pintype "passive"))
      (node (ref "R6") (pin "1") (pinfunction "1_1") (pintype "passive"))
      (node (ref "R9") (pin "1") (pinfunction "1_1") (pintype "passive"))
      (node (ref "U4") (pin "8") (pinfunction "A_8") (pintype "passive"))
    )
    (net (code "91") (name "Net-(U4B-B)") (class "Default")
      (node (ref "C17") (pin "2") (pinfunction "2_2") (pintype "passive"))
      (node (ref "R10") (pin "2") (pinfunction "2_2") (pintype "passive"))
      (node (ref "R7") (pin "2") (pinfunction "2_2") (pintype "passive"))
      (node (ref "U4") (pin "10") (pinfunction "B_10") (pintype "passive"))
    )
    (net (code "92") (name "Net-(U4B-W)") (class "Default")
      (node (ref "C19") (pin "2") (pinfunction "2_2") (pintype "passive"))
      (node (ref "U4") (pin "9") (pinfunction "W_9") (pintype "passive"))
    )
    (net (code "93") (name "Net-(U4C-A)") (class "Default")
      (node (ref "C48") (pin "1") (pinfunction "1_1") (pintype "passive"))
      (node (ref "R29") (pin "1") (pinfunction "1_1") (pintype "passive"))
      (node (ref "R32") (pin "1") (pinfunction "1_1") (pintype "passive"))
      (node (ref "U4") (pin "7") (pinfunction "A_7") (pintype "passive"))
    )
    (net (code "94") (name "Net-(U4C-B)") (class "Default")
      (node (ref "C48") (pin "2") (pinfunction "2_2") (pintype "passive"))
      (node (ref "R30") (pin "2") (pinfunction "2_2") (pintype "passive"))
      (node (ref "R33") (pin "2") (pinfunction "2_2") (pintype "passive"))
      (node (ref "U4") (pin "5") (pinfunction "B_5") (pintype "passive"))
    )
    (net (code "95") (name "Net-(U4C-W)") (class "Default")
      (node (ref "C51") (pin "2") (pinfunction "2_2") (pintype "passive"))
      (node (ref "U4") (pin "6") (pinfunction "W_6") (pintype "passive"))
    )
    (net (code "96") (name "Net-(U5B-A)") (class "Default")
      (node (ref "R14") (pin "1") (pinfunction "1_1") (pintype "passive"))
      (node (ref "U5") (pin "8") (pinfunction "A_8") (pintype "passive"))
    )
    (net (code "97") (name "Net-(U5B-B)") (class "Default")
      (node (ref "R15") (pin "2") (pinfunction "2_2") (pintype "passive"))
      (node (ref "U5") (pin "10") (pinfunction "B_10") (pintype "passive"))
    )
    (net (code "98") (name "Net-(U5B-W)") (class "Default")
      (node (ref "C25") (pin "2") (pinfunction "2_2") (pintype "passive"))
      (node (ref "U5") (pin "9") (pinfunction "W_9") (pintype "passive"))
    )
    (net (code "99") (name "Net-(U5C-A)") (class "Default")
      (node (ref "R37") (pin "1") (pinfunction "1_1") (pintype "passive"))
      (node (ref "U5") (pin "7") (pinfunction "A_7") (pintype "passive"))
    )
    (net (code "100") (name "Net-(U5C-B)") (class "Default")
      (node (ref "R38") (pin "2") (pinfunction "2_2") (pintype "passive"))
      (node (ref "U5") (pin "5") (pinfunction "B_5") (pintype "passive"))
    )
    (net (code "101") (name "Net-(U5C-W)") (class "Default")
      (node (ref "C59") (pin "2") (pinfunction "2_2") (pintype "passive"))
      (node (ref "U5") (pin "6") (pinfunction "W_6") (pintype "passive"))
    )
    (net (code "102") (name "Net-(U6-INNA)") (class "Default")
      (node (ref "C32") (pin "2") (pinfunction "2_2") (pintype "passive"))
      (node (ref "C33") (pin "2") (pinfunction "2_2") (pintype "passive"))
      (node (ref "U6") (pin "23") (pinfunction "INNA_23") (pintype "bidirectional"))
    )
    (net (code "103") (name "Net-(U6-INNB)") (class "Default")
      (node (ref "C40") (pin "2") (pinfunction "2_2") (pintype "passive"))
      (node (ref "C41") (pin "2") (pinfunction "2_2") (pintype "passive"))
      (node (ref "U6") (pin "33") (pinfunction "INNB_33") (pintype "bidirectional"))
    )
    (net (code "104") (name "Net-(U6-INPA)") (class "Default")
      (node (ref "C22") (pin "2") (pinfunction "2_2") (pintype "passive"))
      (node (ref "C27") (pin "2") (pinfunction "2_2") (pintype "passive"))
      (node (ref "U6") (pin "22") (pinfunction "INPA_22") (pintype "bidirectional"))
    )
    (net (code "105") (name "Net-(U6-INPB)") (class "Default")
      (node (ref "C37") (pin "2") (pinfunction "2_2") (pintype "passive"))
      (node (ref "C39") (pin "2") (pinfunction "2_2") (pintype "passive"))
      (node (ref "U6") (pin "32") (pinfunction "INPB_32") (pintype "bidirectional"))
    )
    (net (code "106") (name "Net-(U6-PGND)") (class "Default")
      (node (ref "C49") (pin "2") (pinfunction "2_2") (pintype "passive"))
      (node (ref "U6") (pin "18") (pinfunction "PGND_18") (pintype "bidirectional"))
    )
    (net (code "107") (name "Net-(U6-ROSC)") (class "Default")
      (node (ref "C58") (pin "1") (pinfunction "1_1") (pintype "passive"))
      (node (ref "R41") (pin "2") (pinfunction "2_2") (pintype "passive"))
      (node (ref "U6") (pin "24") (pinfunction "ROSC_24") (pintype "bidirectional"))
    )
    (net (code "108") (name "Net-(U6-SVCC)") (class "Default")
      (node (ref "C52") (pin "1") (pinfunction "1_1") (pintype "passive"))
      (node (ref "U6") (pin "35") (pinfunction "SVCC_35") (pintype "bidirectional"))
    )
    (net (code "109") (name "Net-(U6-SVR)") (class "Default")
      (node (ref "C61") (pin "+") (pinfunction "+_+") (pintype "passive"))
      (node (ref "U6") (pin "29") (pinfunction "SVR_29") (pintype "bidirectional"))
    )
    (net (code "110") (name "Net-(U6-VDDPW)") (class "Default")
      (node (ref "C49") (pin "1") (pinfunction "1_1") (pintype "passive"))
      (node (ref "R27") (pin "1") (pinfunction "1_1") (pintype "passive"))
      (node (ref "U6") (pin "19") (pinfunction "VDDPW_19") (pintype "bidirectional"))
    )
    (net (code "111") (name "Net-(U6-VREF)") (class "Default")
      (node (ref "C60") (pin "+") (pinfunction "+_+") (pintype "passive"))
      (node (ref "U6") (pin "34") (pinfunction "VREF_34") (pintype "bidirectional"))
    )
    (net (code "112") (name "Net-(U6-VSS)") (class "Default")
      (node (ref "C52") (pin "2") (pinfunction "2_2") (pintype "passive"))
      (node (ref "U6") (pin "36") (pinfunction "VSS_36") (pintype "bidirectional"))
    )
    (net (code "113") (name "Net-(U7B-A)") (class "Default")
      (node (ref "U7") (pin "8") (pinfunction "A_8") (pintype "passive"))
      (node (ref "X1") (pin "6") (pinfunction "T2_6") (pintype "passive"))
    )
    (net (code "114") (name "Net-(U7B-W)") (class "Default")
      (node (ref "R28") (pin "1") (pinfunction "1_1") (pintype "passive"))
      (node (ref "U7") (pin "9") (pinfunction "W_9") (pintype "passive"))
    )
    (net (code "115") (name "Net-(U7C-A)") (class "Default")
      (node (ref "U7") (pin "7") (pinfunction "A_7") (pintype "passive"))
      (node (ref "X1") (pin "5") (pinfunction "T1_5") (pintype "passive"))
    )
    (net (code "116") (name "Net-(U7C-W)") (class "Default")
      (node (ref "R35") (pin "1") (pinfunction "1_1") (pintype "passive"))
      (node (ref "U7") (pin "6") (pinfunction "W_6") (pintype "passive"))
    )
    (net (code "117") (name "Net-(U8B-A)") (class "Default")
      (node (ref "U8") (pin "8") (pinfunction "A_8") (pintype "passive"))
      (node (ref "X1") (pin "3") (pinfunction "T2_3") (pintype "passive"))
    )
    (net (code "118") (name "Net-(U8B-W)") (class "Default")
      (node (ref "R11") (pin "1") (pinfunction "1_1") (pintype "passive"))
      (node (ref "U8") (pin "9") (pinfunction "W_9") (pintype "passive"))
    )
    (net (code "119") (name "Net-(U8C-A)") (class "Default")
      (node (ref "U8") (pin "7") (pinfunction "A_7") (pintype "passive"))
      (node (ref "X1") (pin "2") (pinfunction "T1_2") (pintype "passive"))
    )
    (net (code "120") (name "Net-(U8C-W)") (class "Default")
      (node (ref "R19") (pin "1") (pinfunction "1_1") (pintype "passive"))
      (node (ref "U8") (pin "6") (pinfunction "W_6") (pintype "passive"))
    )
    (net (code "121") (name "PE") (class "Default")
      (node (ref "H1") (pin "B3,0") (pinfunction "MOUNT_B3,0") (pintype "passive"))
      (node (ref "H2") (pin "B3,0") (pinfunction "MOUNT_B3,0") (pintype "passive"))
      (node (ref "H3") (pin "B3,0") (pinfunction "MOUNT_B3,0") (pintype "passive"))
      (node (ref "H4") (pin "B3,0") (pinfunction "MOUNT_B3,0") (pintype "passive"))
      (node (ref "J4") (pin "P$1") (pinfunction "P$1_P$1") (pintype "bidirectional"))
      (node (ref "J4") (pin "P$2") (pinfunction "P$1_P$2") (pintype "bidirectional"))
      (node (ref "J9") (pin "S1") (pinfunction "SHIELD_S1") (pintype "bidirectional"))
      (node (ref "J9") (pin "S2") (pinfunction "SHIELD_S2") (pintype "bidirectional"))
      (node (ref "J9") (pin "S3") (pinfunction "SHIELD_S3") (pintype "bidirectional"))
      (node (ref "J9") (pin "S4") (pinfunction "SHIELD_S4") (pintype "bidirectional"))
      (node (ref "U6") (pin "1") (pinfunction "SUB_GND_1") (pintype "bidirectional"))
    )
    (net (code "122") (name "PWR_BTN") (class "Default")
      (node (ref "IC6") (pin "1") (pinfunction "PD3(INT1)_1") (pintype "bidirectional"))
      (node (ref "X2") (pin "2") (pinfunction "2_2") (pintype "passive"))
    )
    (net (code "123") (name "R_OUT+") (class "Default")
      (node (ref "C30") (pin "1") (pinfunction "1_1") (pintype "passive"))
      (node (ref "C35") (pin "1") (pinfunction "1_1") (pintype "passive"))
      (node (ref "K2") (pin "S2") (pinfunction "S_S2") (pintype "passive"))
      (node (ref "L1") (pin "2") (pinfunction "2_2") (pintype "passive"))
      (node (ref "R16") (pin "2") (pinfunction "2_2") (pintype "passive"))
    )
    (net (code "124") (name "R_OUT-") (class "Default")
      (node (ref "C35") (pin "2") (pinfunction "2_2") (pintype "passive"))
      (node (ref "C36") (pin "2") (pinfunction "2_2") (pintype "passive"))
      (node (ref "J5") (pin "2") (pinfunction "P$1_2") (pintype "bidirectional"))
      (node (ref "L2") (pin "2") (pinfunction "2_2") (pintype "passive"))
      (node (ref "R22") (pin "1") (pinfunction "1_1") (pintype "passive"))
    )
    (net (code "125") (name "SCL") (class "Default")
      (node (ref "IC6") (pin "28") (pinfunction "PC5(ADC5/SCL)_28") (pintype "bidirectional"))
      (node (ref "IC7") (pin "3") (pinfunction "I_3") (pintype "input"))
      (node (ref "R52") (pin "1") (pinfunction "1_1") (pintype "passive"))
      (node (ref "U2") (pin "2") (pinfunction "SCL_2") (pintype "bidirectional"))
      (node (ref "U3") (pin "2") (pinfunction "SCL_2") (pintype "bidirectional"))
      (node (ref "U4") (pin "2") (pinfunction "SCL_2") (pintype "bidirectional"))
      (node (ref "U5") (pin "2") (pinfunction "SCL_2") (pintype "bidirectional"))
      (node (ref "U7") (pin "2") (pinfunction "SCL_2") (pintype "bidirectional"))
      (node (ref "U8") (pin "2") (pinfunction "SCL_2") (pintype "bidirectional"))
    )
    (net (code "126") (name "SDA") (class "Default")
      (node (ref "IC6") (pin "27") (pinfunction "PC4(ADC4/SDA)_27") (pintype "bidirectional"))
      (node (ref "IC7") (pin "1") (pinfunction "I_1") (pintype "input"))
      (node (ref "R2") (pin "1") (pinfunction "1_1") (pintype "passive"))
      (node (ref "U2") (pin "3") (pinfunction "SDA_3") (pintype "bidirectional"))
      (node (ref "U3") (pin "3") (pinfunction "SDA_3") (pintype "bidirectional"))
      (node (ref "U4") (pin "3") (pinfunction "SDA_3") (pintype "bidirectional"))
      (node (ref "U5") (pin "3") (pinfunction "SDA_3") (pintype "bidirectional"))
      (node (ref "U7") (pin "3") (pinfunction "SDA_3") (pintype "bidirectional"))
      (node (ref "U8") (pin "3") (pinfunction "SDA_3") (pintype "bidirectional"))
    )
    (net (code "127") (name "SPK_PROTECT") (class "Default")
      (node (ref "IC6") (pin "11") (pinfunction "PD7(AIN1)_11") (pintype "bidirectional"))
      (node (ref "T2") (pin "B") (pinfunction "B_B") (pintype "passive"))
    )
    (net (code "128") (name "unconnected-(IC6-ADC6-Pad19)") (class "Default")
      (node (ref "IC6") (pin "19") (pinfunction "ADC6_19") (pintype "bidirectional"))
    )
    (net (code "129") (name "unconnected-(IC6-ADC7-Pad22)") (class "Default")
      (node (ref "IC6") (pin "22") (pinfunction "ADC7_22") (pintype "bidirectional"))
    )
    (net (code "130") (name "unconnected-(IC6-PB6(XTAL1{slash}TOSC1)-Pad7)") (class "Default")
      (node (ref "IC6") (pin "7") (pinfunction "PB6(XTAL1/TOSC1)_7") (pintype "bidirectional"))
    )
    (net (code "131") (name "unconnected-(IC6-PB7(XTAL2{slash}TOSC2)-Pad8)") (class "Default")
      (node (ref "IC6") (pin "8") (pinfunction "PB7(XTAL2/TOSC2)_8") (pintype "bidirectional"))
    )
    (net (code "132") (name "unconnected-(IC7C-O-Pad6)") (class "Default")
      (node (ref "IC7") (pin "6") (pinfunction "O_6") (pintype "output"))
    )
    (net (code "133") (name "unconnected-(IC7D-O-Pad8)") (class "Default")
      (node (ref "IC7") (pin "8") (pinfunction "O_8") (pintype "output"))
    )
    (net (code "134") (name "unconnected-(J9-PadD+)") (class "Default")
      (node (ref "J9") (pin "D+") (pinfunction "D+_D+") (pintype "bidirectional"))
    )
    (net (code "135") (name "unconnected-(J9-PadD-)") (class "Default")
      (node (ref "J9") (pin "D-") (pinfunction "D-_D-") (pintype "bidirectional"))
    )
    (net (code "136") (name "unconnected-(K2B-O-PadO1)") (class "Default")
      (node (ref "K2") (pin "O1") (pinfunction "O_O1") (pintype "passive"))
    )
    (net (code "137") (name "unconnected-(K2C-O-PadO2)") (class "Default")
      (node (ref "K2") (pin "O2") (pinfunction "O_O2") (pintype "passive"))
    )
    (net (code "138") (name "unconnected-(U2A-~{WP}-Pad11)") (class "Default")
      (node (ref "U2") (pin "11") (pinfunction "~{WP}_11") (pintype "bidirectional"))
    )
    (net (code "139") (name "unconnected-(U3A-~{WP}-Pad11)") (class "Default")
      (node (ref "U3") (pin "11") (pinfunction "~{WP}_11") (pintype "bidirectional"))
    )
    (net (code "140") (name "unconnected-(U4A-~{WP}-Pad11)") (class "Default")
      (node (ref "U4") (pin "11") (pinfunction "~{WP}_11") (pintype "bidirectional"))
    )
    (net (code "141") (name "unconnected-(U5A-~{WP}-Pad11)") (class "Default")
      (node (ref "U5") (pin "11") (pinfunction "~{WP}_11") (pintype "bidirectional"))
    )
    (net (code "142") (name "unconnected-(U6-SYNCLK-Pad25)") (class "Default")
      (node (ref "U6") (pin "25") (pinfunction "SYNCLK_25") (pintype "bidirectional"))
    )
    (net (code "143") (name "unconnected-(U7A-~{WP}-Pad11)") (class "Default")
      (node (ref "U7") (pin "11") (pinfunction "~{WP}_11") (pintype "bidirectional"))
    )
    (net (code "144") (name "unconnected-(U8A-~{WP}-Pad11)") (class "Default")
      (node (ref "U8") (pin "11") (pinfunction "~{WP}_11") (pintype "bidirectional"))
    )
  )
)
